# HLK-7621-ALL-KIT-V1_0_020_2_25.net
KiCad netlist of a schematic drawn in Altium Designer
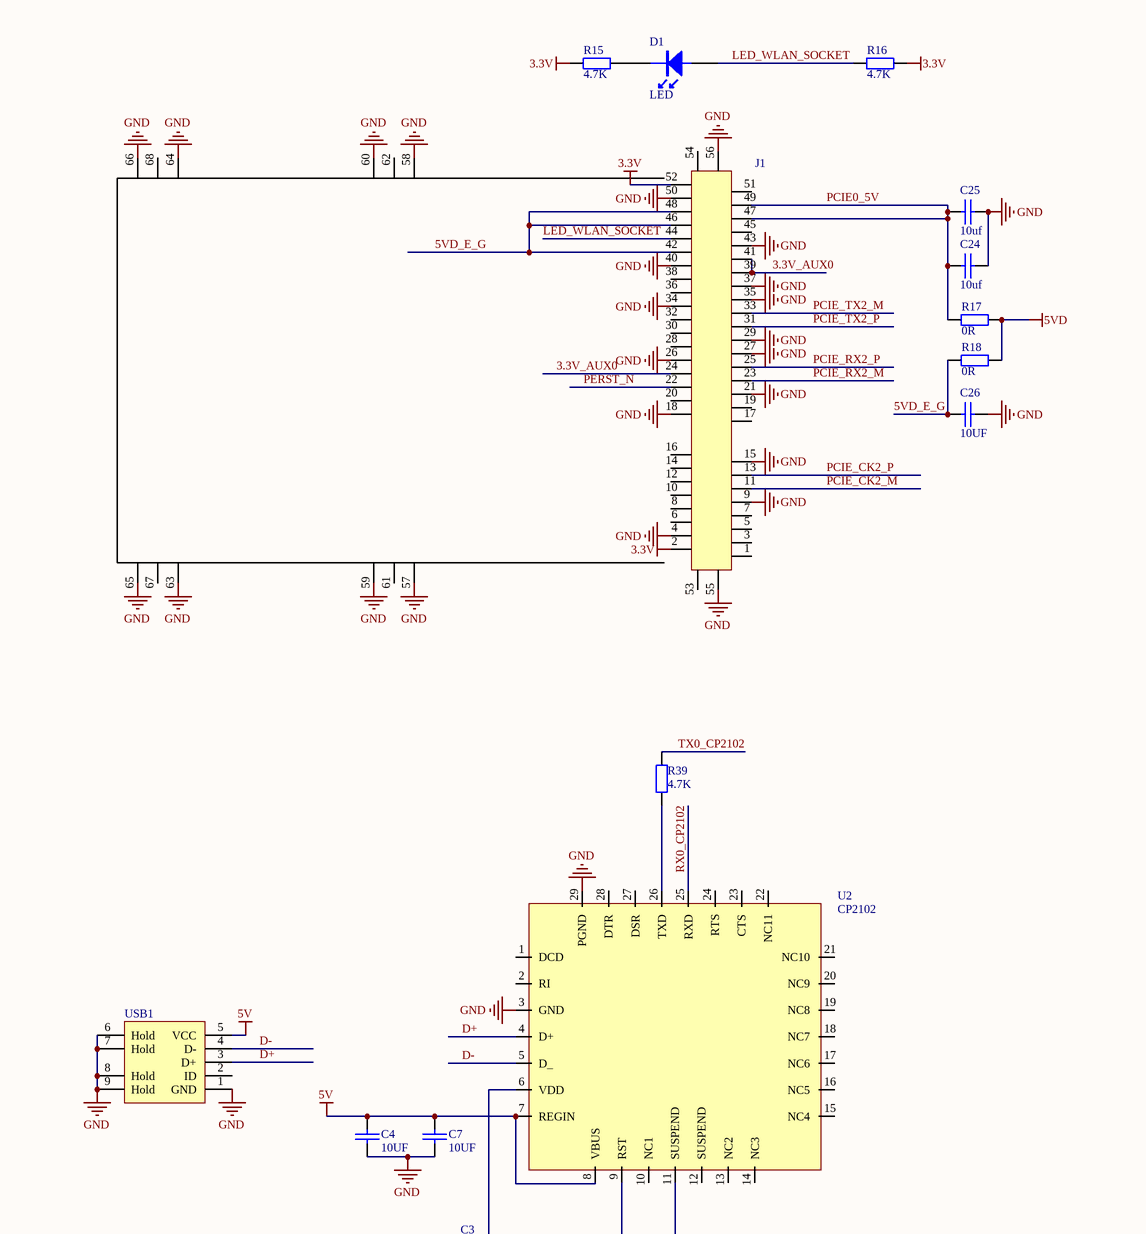
[diagram p0: HLK-7621-ALL-KIT-V1.0(020.2.25).SchDoc, top left]
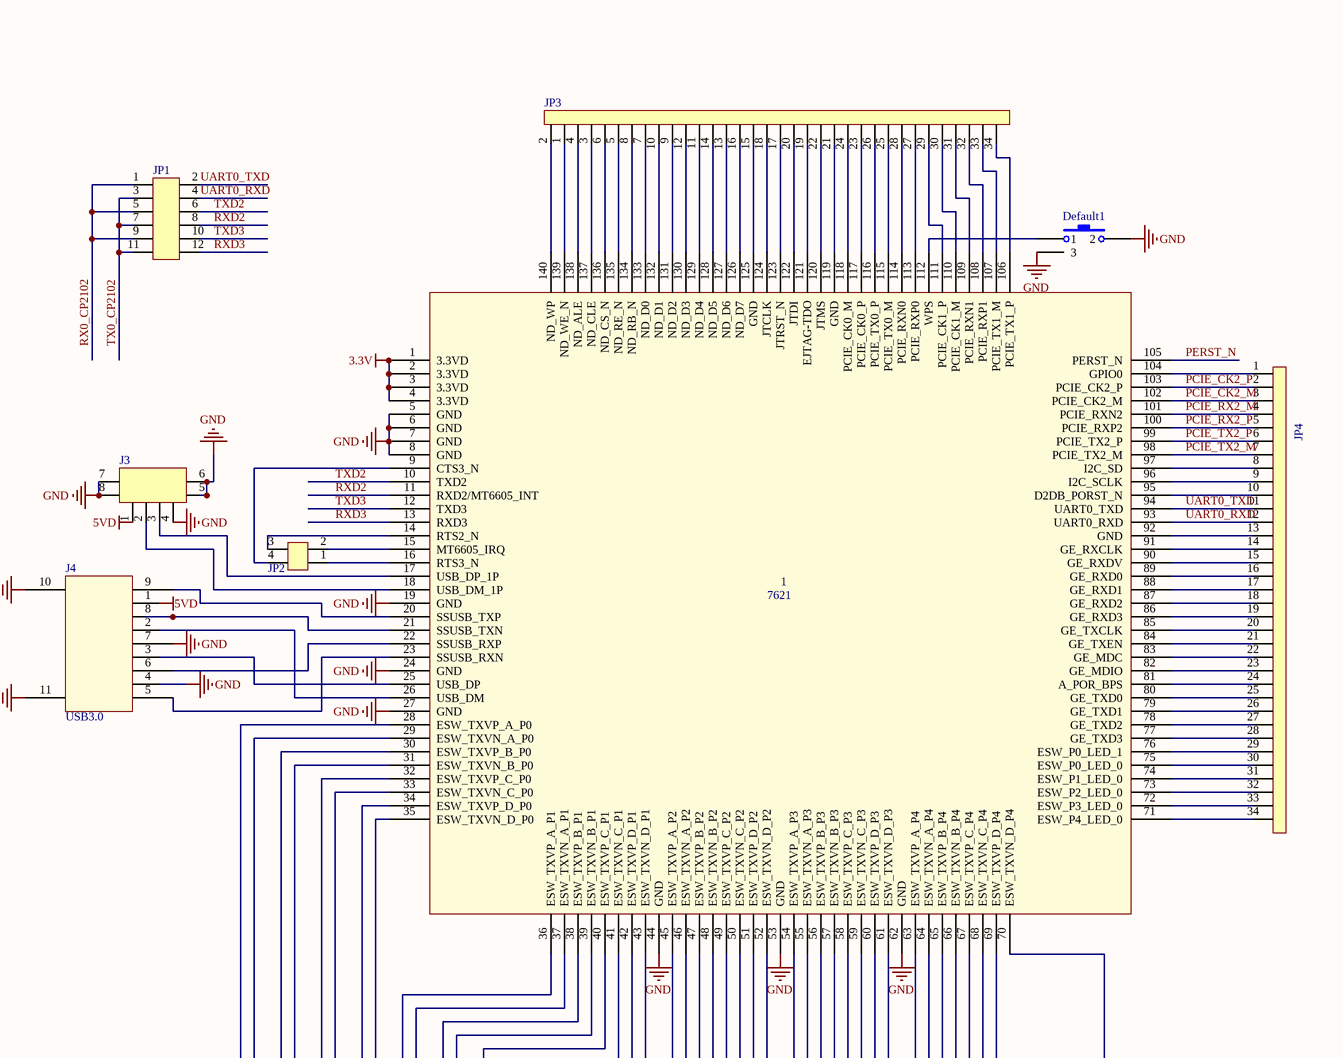
[diagram p1: HLK-7621-ALL-KIT-V1.0(020.2.25).SchDoc, top right]
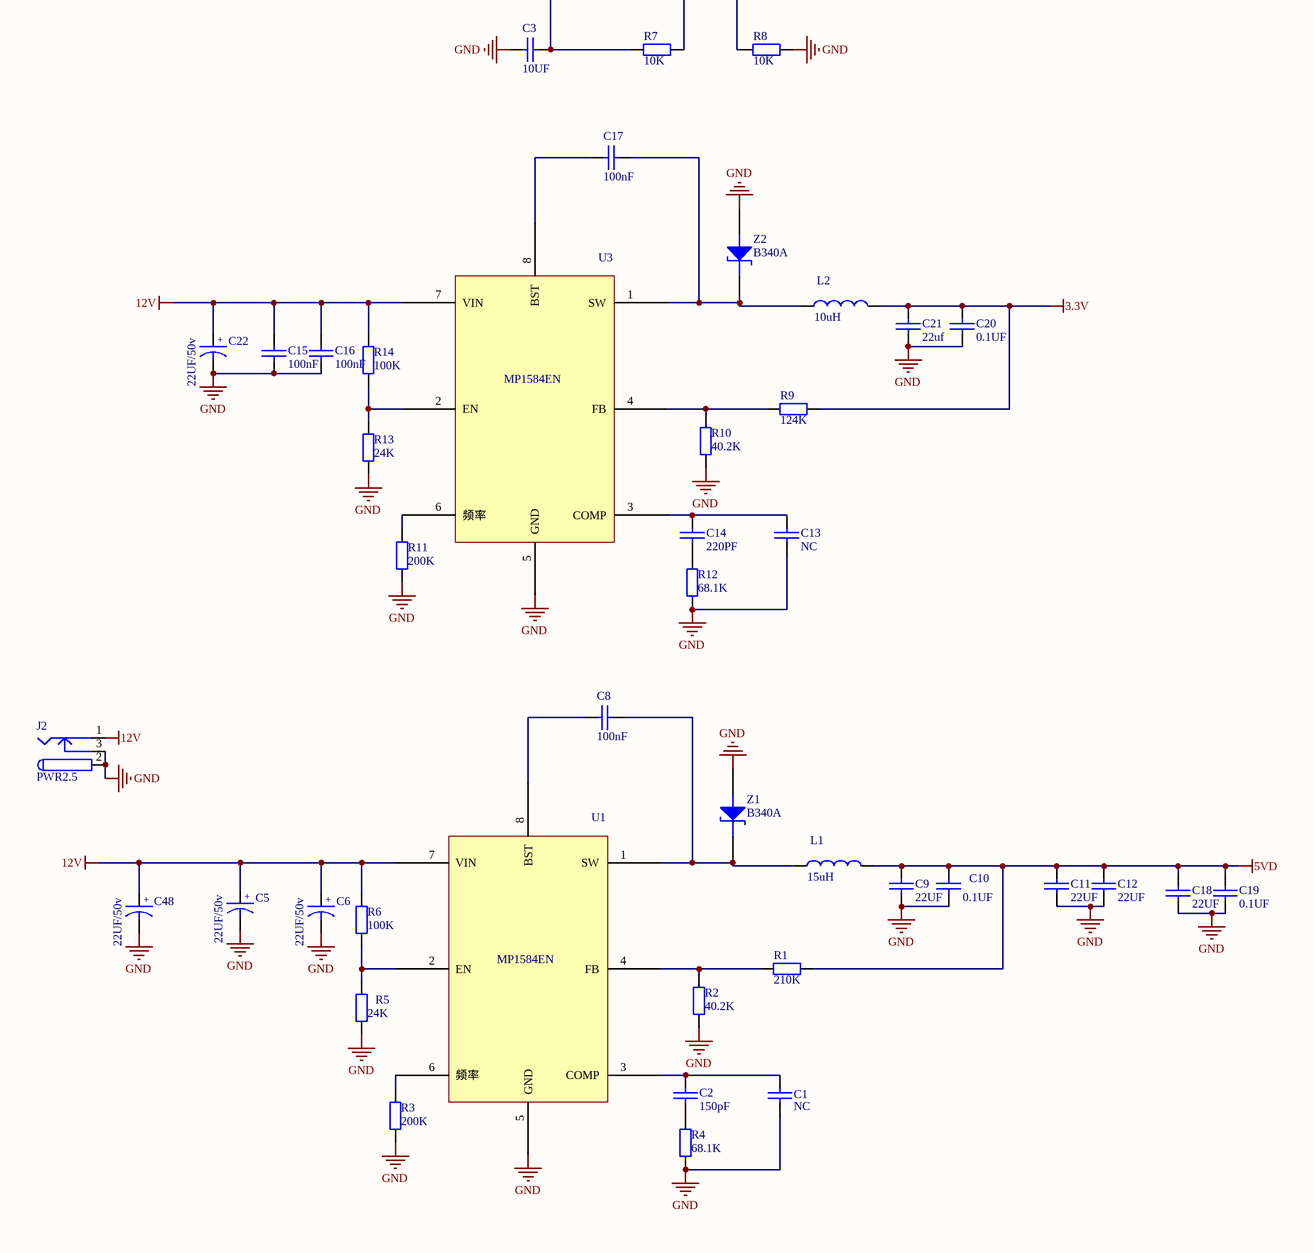
[diagram p2: HLK-7621-ALL-KIT-V1.0(020.2.25).SchDoc, bottom left]
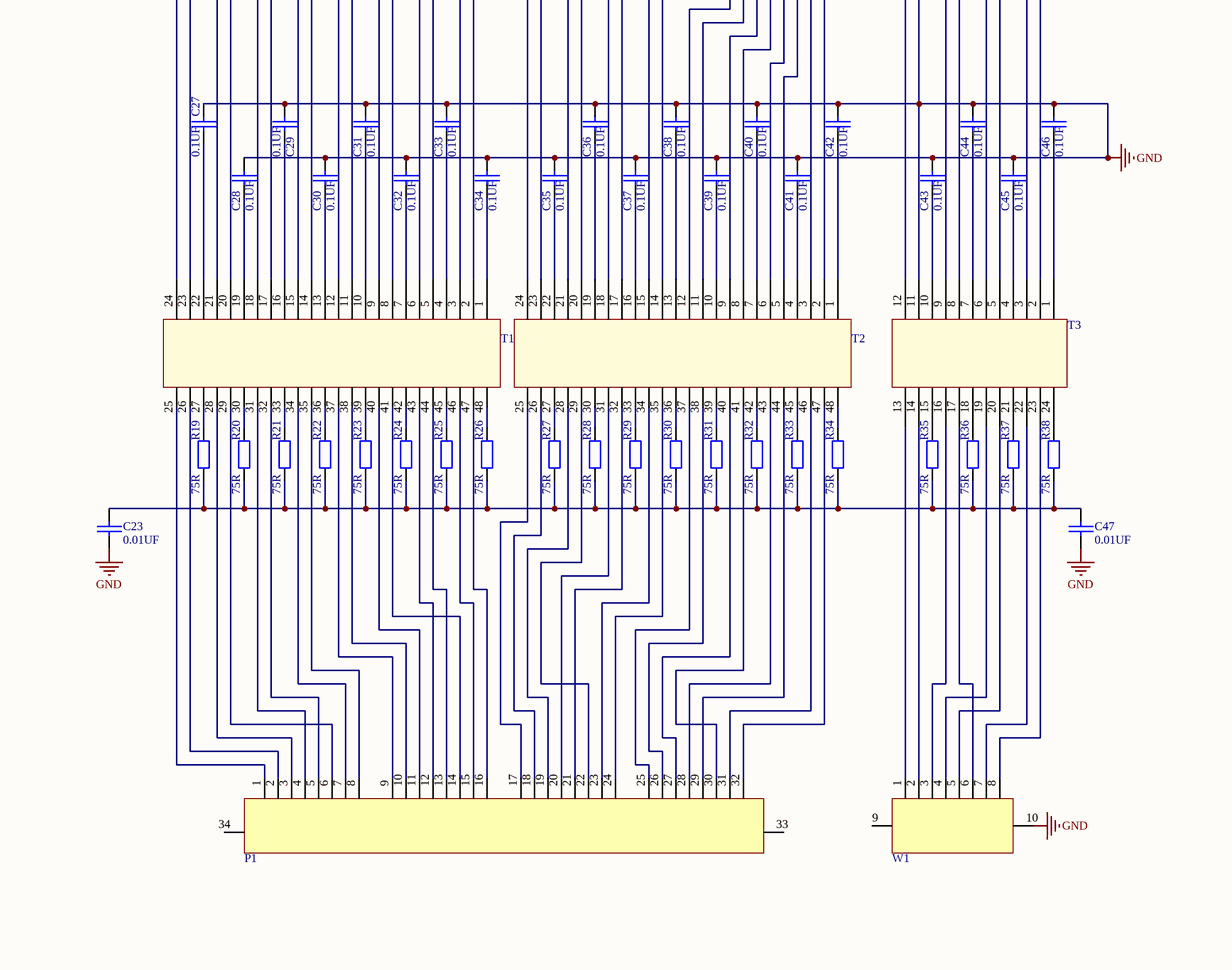
[diagram p3: HLK-7621-ALL-KIT-V1.0(020.2.25).SchDoc, bottom right]

(export (version "E")
  (design (tool "Eeschema 10.0.6"))
  (components
    (comp (ref "1") (value "7621") (footprint "HLK-7621") (libsource (lib "Schlib1") (part "7621")))
    (comp (ref "C1")
      (value "NC")
      (footprint "0603")
      (description "Capacitor")
      (libsource (lib "*") (part "CAP"))
    )
    (comp (ref "C2")
      (value "150pF")
      (footprint "0603")
      (description "Capacitor")
      (libsource (lib "*") (part "CAP"))
    )
    (comp (ref "C3")
      (value "10UF")
      (footprint "0603L")
      (description "Capacitor")
      (libsource (lib "*") (part "CAP"))
    )
    (comp (ref "C4")
      (value "10UF")
      (footprint "0603L")
      (description "Capacitor")
      (libsource (lib "*") (part "CAP"))
    )
    (comp (ref "C5")
      (value "22UF/50v")
      (footprint "0603")
      (description "Capacitor")
      (libsource (lib "Miscellaneous Devices") (part "CAPACITOR POL"))
    )
    (comp (ref "C6")
      (value "22UF/50v")
      (footprint "0603")
      (description "Capacitor")
      (libsource (lib "Miscellaneous Devices") (part "CAPACITOR POL"))
    )
    (comp (ref "C7")
      (value "10UF")
      (footprint "0603L")
      (description "Capacitor")
      (libsource (lib "*") (part "CAP"))
    )
    (comp (ref "C8")
      (value "100nF")
      (footprint "0603")
      (description "Capacitor")
      (libsource (lib "*") (part "CAP"))
    )
    (comp (ref "C9")
      (value "22UF")
      (footprint "0603")
      (description "Capacitor")
      (libsource (lib "*") (part "CAP"))
    )
    (comp (ref "C10")
      (value "0.1UF")
      (footprint "0603")
      (description "Capacitor")
      (libsource (lib "*") (part "CAP"))
    )
    (comp (ref "C11")
      (value "22UF")
      (footprint "0603")
      (description "Capacitor")
      (libsource (lib "*") (part "CAP"))
    )
    (comp (ref "C12")
      (value "22UF")
      (footprint "0603")
      (description "Capacitor")
      (libsource (lib "*") (part "CAP"))
    )
    (comp (ref "C13")
      (value "NC")
      (footprint "0603")
      (description "Capacitor")
      (libsource (lib "*") (part "CAP"))
    )
    (comp (ref "C14")
      (value "220PF")
      (footprint "0603")
      (description "Capacitor")
      (libsource (lib "*") (part "CAP"))
    )
    (comp (ref "C15")
      (value "100nF")
      (footprint "0603")
      (description "Capacitor")
      (libsource (lib "*") (part "CAP"))
    )
    (comp (ref "C16")
      (value "100nF")
      (footprint "0603")
      (description "Capacitor")
      (libsource (lib "*") (part "CAP"))
    )
    (comp (ref "C17")
      (value "100nF")
      (footprint "0603")
      (description "Capacitor")
      (libsource (lib "*") (part "CAP"))
    )
    (comp (ref "C18")
      (value "22UF")
      (footprint "0603")
      (description "Capacitor")
      (libsource (lib "*") (part "CAP"))
    )
    (comp (ref "C19")
      (value "0.1UF")
      (footprint "0603")
      (description "Capacitor")
      (libsource (lib "*") (part "CAP"))
    )
    (comp (ref "C20")
      (value "0.1UF")
      (footprint "0603")
      (description "Capacitor")
      (libsource (lib "*") (part "CAP"))
    )
    (comp (ref "C21")
      (value "22uf")
      (footprint "0603")
      (description "Capacitor")
      (libsource (lib "*") (part "CAP"))
    )
    (comp (ref "C22")
      (value "22UF/50v")
      (footprint "CAP_SMT_8*10.5")
      (description "Capacitor")
      (libsource (lib "Miscellaneous Devices") (part "CAPACITOR POL"))
    )
    (comp (ref "C23")
      (value "0.01UF")
      (footprint "C1206")
      (description "Capacitor")
      (libsource (lib "*") (part "CAP"))
    )
    (comp (ref "C24")
      (value "10uf")
      (footprint "C1206")
      (description "Capacitor")
      (libsource (lib "*") (part "CAP"))
    )
    (comp (ref "C25")
      (value "10uf")
      (footprint "C1206")
      (description "Capacitor")
      (libsource (lib "*") (part "CAP"))
    )
    (comp (ref "C26")
      (value "10UF")
      (footprint "C1206")
      (description "Capacitor")
      (libsource (lib "*") (part "CAP"))
    )
    (comp (ref "C27")
      (value "0.1UF")
      (footprint "C0402")
      (description "Capacitor")
      (libsource (lib "*") (part "CAP"))
    )
    (comp (ref "C28")
      (value "0.1UF")
      (footprint "C0402")
      (description "Capacitor")
      (libsource (lib "*") (part "CAP"))
    )
    (comp (ref "C29")
      (value "0.1UF")
      (footprint "C0402")
      (description "Capacitor")
      (libsource (lib "*") (part "CAP"))
    )
    (comp (ref "C30")
      (value "0.1UF")
      (footprint "C0402")
      (description "Capacitor")
      (libsource (lib "*") (part "CAP"))
    )
    (comp (ref "C31")
      (value "0.1UF")
      (footprint "C0402")
      (description "Capacitor")
      (libsource (lib "*") (part "CAP"))
    )
    (comp (ref "C32")
      (value "0.1UF")
      (footprint "C0402")
      (description "Capacitor")
      (libsource (lib "*") (part "CAP"))
    )
    (comp (ref "C33")
      (value "0.1UF")
      (footprint "C0402")
      (description "Capacitor")
      (libsource (lib "*") (part "CAP"))
    )
    (comp (ref "C34")
      (value "0.1UF")
      (footprint "C0402")
      (description "Capacitor")
      (libsource (lib "*") (part "CAP"))
    )
    (comp (ref "C35")
      (value "0.1UF")
      (footprint "C0402")
      (description "Capacitor")
      (libsource (lib "*") (part "CAP"))
    )
    (comp (ref "C36")
      (value "0.1UF")
      (footprint "C0402")
      (description "Capacitor")
      (libsource (lib "*") (part "CAP"))
    )
    (comp (ref "C37")
      (value "0.1UF")
      (footprint "C0402")
      (description "Capacitor")
      (libsource (lib "*") (part "CAP"))
    )
    (comp (ref "C38")
      (value "0.1UF")
      (footprint "C0402")
      (description "Capacitor")
      (libsource (lib "*") (part "CAP"))
    )
    (comp (ref "C39")
      (value "0.1UF")
      (footprint "C0402")
      (description "Capacitor")
      (libsource (lib "*") (part "CAP"))
    )
    (comp (ref "C40")
      (value "0.1UF")
      (footprint "C0402")
      (description "Capacitor")
      (libsource (lib "*") (part "CAP"))
    )
    (comp (ref "C41")
      (value "0.1UF")
      (footprint "C0402")
      (description "Capacitor")
      (libsource (lib "*") (part "CAP"))
    )
    (comp (ref "C42")
      (value "0.1UF")
      (footprint "C0402")
      (description "Capacitor")
      (libsource (lib "*") (part "CAP"))
    )
    (comp (ref "C43")
      (value "0.1UF")
      (footprint "C0402")
      (description "Capacitor")
      (libsource (lib "*") (part "CAP"))
    )
    (comp (ref "C44")
      (value "0.1UF")
      (footprint "C0402")
      (description "Capacitor")
      (libsource (lib "*") (part "CAP"))
    )
    (comp (ref "C45")
      (value "0.1UF")
      (footprint "C0402")
      (description "Capacitor")
      (libsource (lib "*") (part "CAP"))
    )
    (comp (ref "C46")
      (value "0.1UF")
      (footprint "C0402")
      (description "Capacitor")
      (libsource (lib "*") (part "CAP"))
    )
    (comp (ref "C47")
      (value "0.01UF")
      (footprint "C1206")
      (description "Capacitor")
      (libsource (lib "*") (part "CAP"))
    )
    (comp (ref "C48")
      (value "22UF/50v")
      (footprint "CAP_SMT_8*10.5")
      (description "Capacitor")
      (libsource (lib "Miscellaneous Devices") (part "CAPACITOR POL"))
    )
    (comp (ref "D1") (value "LED") (footprint "C1206") (libsource (lib "*") (part "LED")))
    (comp (ref "Default1")
      (value "SW-PB")
      (footprint "K5")
      (description "Switch")
      (fields (field (name "PUBLISHER") "Altium Limited"))
      (libsource (lib "Miscellaneous Devices") (part "SW-PB"))
    )
    (comp (ref "J1")
      (value "~")
      (footprint "CONSG/54/MINICARD/AS0B22-S68-7F/HALF/FUL")
      (libsource (lib "") (part "Component_1_2"))
    )
    (comp (ref "J2")
      (value "PWR2.5")
      (description "Low Voltage Power Supply Connector")
      (fields (field (name "PUBLISHER") "Altium Limited"))
      (libsource (lib "*") (part "PWR2.5"))
    )
    (comp (ref "J3") (value "~") (libsource (lib "Schlib1") (part "2")))
    (comp (ref "J4") (value "USB3.0") (libsource (lib "Schlib1") (part "USB3.0/9P/DIP/MAINSUPER")))
    (comp (ref "JP1") (value "~") (footprint "HDR2X6") (libsource (lib "Schlib1") (part "Component_1")))
    (comp (ref "JP2") (value "~") (footprint "HDR2X2") (libsource (lib "") (part "2_1")))
    (comp (ref "JP3") (value "~") (footprint "HDR2X17") (libsource (lib "") (part "2_2")))
    (comp (ref "JP4") (value "2") (footprint "HDR2X17") (libsource (lib "") (part "2_3")))
    (comp (ref "L1") (value "15uH") (footprint "CD105") (libsource (lib "startkit") (part "INDUCTOR1")))
    (comp (ref "L2") (value "10uH") (footprint "CD105") (libsource (lib "startkit") (part "INDUCTOR1")))
    (comp (ref "P1")
      (value "Component_2")
      (footprint "PHJ8X4_N")
      (libsource (lib "Schlib1") (part "Component_2"))
    )
    (comp (ref "R1")
      (value "210K")
      (footprint "0603")
      (description "Resistor")
      (fields (field (name "PUBLISHER") "Altium Limited"))
      (libsource (lib "Miscellaneous Devices") (part "Res2"))
    )
    (comp (ref "R2")
      (value "40.2K")
      (footprint "0603")
      (description "Resistor")
      (fields (field (name "PUBLISHER") "Altium Limited"))
      (libsource (lib "") (part "Res2_1"))
    )
    (comp (ref "R3")
      (value "200K")
      (footprint "0603")
      (description "Resistor")
      (fields (field (name "PUBLISHER") "Altium Limited"))
      (libsource (lib "") (part "Res2_1"))
    )
    (comp (ref "R4")
      (value "68.1K")
      (footprint "0603")
      (description "Resistor")
      (fields (field (name "PUBLISHER") "Altium Limited"))
      (libsource (lib "") (part "Res2_1"))
    )
    (comp (ref "R5")
      (value "24K")
      (footprint "0603")
      (description "Resistor")
      (fields (field (name "PUBLISHER") "Altium Limited"))
      (libsource (lib "") (part "Res2_1"))
    )
    (comp (ref "R6")
      (value "100K")
      (footprint "0603")
      (description "Resistor")
      (fields (field (name "PUBLISHER") "Altium Limited"))
      (libsource (lib "") (part "Res2_1"))
    )
    (comp (ref "R7")
      (value "10K")
      (footprint "0603L")
      (description "Resistor")
      (fields (field (name "PUBLISHER") "Altium Limited"))
      (libsource (lib "") (part "Res2_2"))
    )
    (comp (ref "R8")
      (value "10K")
      (footprint "0603L")
      (description "Resistor")
      (fields (field (name "PUBLISHER") "Altium Limited"))
      (libsource (lib "Miscellaneous Devices") (part "Res2"))
    )
    (comp (ref "R9")
      (value "124K")
      (footprint "0603")
      (description "Resistor")
      (fields (field (name "PUBLISHER") "Altium Limited"))
      (libsource (lib "Miscellaneous Devices") (part "Res2"))
    )
    (comp (ref "R10")
      (value "40.2K")
      (footprint "0603")
      (description "Resistor")
      (fields (field (name "PUBLISHER") "Altium Limited"))
      (libsource (lib "") (part "Res2_1"))
    )
    (comp (ref "R11")
      (value "200K")
      (footprint "0603")
      (description "Resistor")
      (fields (field (name "PUBLISHER") "Altium Limited"))
      (libsource (lib "") (part "Res2_1"))
    )
    (comp (ref "R12")
      (value "68.1K")
      (footprint "0603")
      (description "Resistor")
      (fields (field (name "PUBLISHER") "Altium Limited"))
      (libsource (lib "") (part "Res2_1"))
    )
    (comp (ref "R13")
      (value "24K")
      (footprint "0603")
      (description "Resistor")
      (fields (field (name "PUBLISHER") "Altium Limited"))
      (libsource (lib "") (part "Res2_1"))
    )
    (comp (ref "R14")
      (value "100K")
      (footprint "0603")
      (description "Resistor")
      (fields (field (name "PUBLISHER") "Altium Limited"))
      (libsource (lib "") (part "Res2_1"))
    )
    (comp (ref "R15")
      (value "4.7K")
      (footprint "0603")
      (description "Resistor")
      (fields (field (name "PUBLISHER") "Altium Limited"))
      (libsource (lib "Miscellaneous Devices") (part "Res2"))
    )
    (comp (ref "R16")
      (value "4.7K")
      (footprint "0603")
      (description "Resistor")
      (fields (field (name "PUBLISHER") "Altium Limited"))
      (libsource (lib "Miscellaneous Devices") (part "Res2"))
    )
    (comp (ref "R17")
      (value "0R")
      (footprint "L0805")
      (description "Resistor")
      (fields (field (name "PUBLISHER") "Altium Limited"))
      (libsource (lib "") (part "Res2_2"))
    )
    (comp (ref "R18")
      (value "0R")
      (footprint "R1206")
      (description "Resistor")
      (fields (field (name "PUBLISHER") "Altium Limited"))
      (libsource (lib "Miscellaneous Devices") (part "Res2"))
    )
    (comp (ref "R19")
      (value "75R")
      (footprint "R0402")
      (description "Resistor")
      (fields (field (name "PUBLISHER") "Altium Limited"))
      (libsource (lib "Schlib1") (part "Res2"))
    )
    (comp (ref "R20")
      (value "75R")
      (footprint "R0402")
      (description "Resistor")
      (fields (field (name "PUBLISHER") "Altium Limited"))
      (libsource (lib "Schlib1") (part "Res2"))
    )
    (comp (ref "R21")
      (value "75R")
      (footprint "R0402")
      (description "Resistor")
      (fields (field (name "PUBLISHER") "Altium Limited"))
      (libsource (lib "Schlib1") (part "Res2"))
    )
    (comp (ref "R22")
      (value "75R")
      (footprint "R0402")
      (description "Resistor")
      (fields (field (name "PUBLISHER") "Altium Limited"))
      (libsource (lib "Schlib1") (part "Res2"))
    )
    (comp (ref "R23")
      (value "75R")
      (footprint "R0402")
      (description "Resistor")
      (fields (field (name "PUBLISHER") "Altium Limited"))
      (libsource (lib "Schlib1") (part "Res2"))
    )
    (comp (ref "R24")
      (value "75R")
      (footprint "R0402")
      (description "Resistor")
      (fields (field (name "PUBLISHER") "Altium Limited"))
      (libsource (lib "Schlib1") (part "Res2"))
    )
    (comp (ref "R25")
      (value "75R")
      (footprint "R0402")
      (description "Resistor")
      (fields (field (name "PUBLISHER") "Altium Limited"))
      (libsource (lib "Schlib1") (part "Res2"))
    )
    (comp (ref "R26")
      (value "75R")
      (footprint "R0402")
      (description "Resistor")
      (fields (field (name "PUBLISHER") "Altium Limited"))
      (libsource (lib "Schlib1") (part "Res2"))
    )
    (comp (ref "R27")
      (value "75R")
      (footprint "R0402")
      (description "Resistor")
      (fields (field (name "PUBLISHER") "Altium Limited"))
      (libsource (lib "Schlib1") (part "Res2"))
    )
    (comp (ref "R28")
      (value "75R")
      (footprint "R0402")
      (description "Resistor")
      (fields (field (name "PUBLISHER") "Altium Limited"))
      (libsource (lib "Schlib1") (part "Res2"))
    )
    (comp (ref "R29")
      (value "75R")
      (footprint "R0402")
      (description "Resistor")
      (fields (field (name "PUBLISHER") "Altium Limited"))
      (libsource (lib "Schlib1") (part "Res2"))
    )
    (comp (ref "R30")
      (value "75R")
      (footprint "R0402")
      (description "Resistor")
      (fields (field (name "PUBLISHER") "Altium Limited"))
      (libsource (lib "Schlib1") (part "Res2"))
    )
    (comp (ref "R31")
      (value "75R")
      (footprint "R0402")
      (description "Resistor")
      (fields (field (name "PUBLISHER") "Altium Limited"))
      (libsource (lib "Schlib1") (part "Res2"))
    )
    (comp (ref "R32")
      (value "75R")
      (footprint "R0402")
      (description "Resistor")
      (fields (field (name "PUBLISHER") "Altium Limited"))
      (libsource (lib "Schlib1") (part "Res2"))
    )
    (comp (ref "R33")
      (value "75R")
      (footprint "R0402")
      (description "Resistor")
      (fields (field (name "PUBLISHER") "Altium Limited"))
      (libsource (lib "Schlib1") (part "Res2"))
    )
    (comp (ref "R34")
      (value "75R")
      (footprint "R0402")
      (description "Resistor")
      (fields (field (name "PUBLISHER") "Altium Limited"))
      (libsource (lib "Schlib1") (part "Res2"))
    )
    (comp (ref "R35")
      (value "75R")
      (footprint "R0402")
      (description "Resistor")
      (fields (field (name "PUBLISHER") "Altium Limited"))
      (libsource (lib "Schlib1") (part "Res2"))
    )
    (comp (ref "R36")
      (value "75R")
      (footprint "R0402")
      (description "Resistor")
      (fields (field (name "PUBLISHER") "Altium Limited"))
      (libsource (lib "Schlib1") (part "Res2"))
    )
    (comp (ref "R37")
      (value "75R")
      (footprint "R0402")
      (description "Resistor")
      (fields (field (name "PUBLISHER") "Altium Limited"))
      (libsource (lib "Schlib1") (part "Res2"))
    )
    (comp (ref "R38")
      (value "75R")
      (footprint "R0402")
      (description "Resistor")
      (fields (field (name "PUBLISHER") "Altium Limited"))
      (libsource (lib "Schlib1") (part "Res2"))
    )
    (comp (ref "R39")
      (value "4.7K")
      (footprint "0603")
      (description "Resistor")
      (fields (field (name "PUBLISHER") "Altium Limited"))
      (libsource (lib "") (part "Res2_3"))
    )
    (comp (ref "T1")
      (value "TRANSFORMER/24P/SMD/HN2429CG")
      (footprint "TRANSFORMER/48P/SMD/GS5014LF")
      (libsource (lib "Schlib1") (part "TRANSFORMER/24P/SMD/HN2429CG"))
    )
    (comp (ref "T2")
      (value "TRANSFORMER/24P/SMD/HN2429CG")
      (footprint "TRANSFORMER/48P/SMD/GS5014LF")
      (libsource (lib "Schlib1") (part "TRANSFORMER/24P/SMD/HN2429CG"))
    )
    (comp (ref "T3")
      (value "TRANSFORMER/24P/SMD/HN2429CG")
      (footprint "TRANSFORMER/24P/SMD/HN2429CG")
      (libsource (lib "") (part "TRANSFORMER/24P/SMD/HN2429CG_1"))
    )
    (comp (ref "U1") (value "MP1584EN") (footprint "SOP8_150") (libsource (lib "") (part "Component_1_1")))
    (comp (ref "U2") (value "CP2102") (footprint "cp2102") (libsource (lib "") (part "Component_1_3")))
    (comp (ref "U3") (value "MP1584EN") (footprint "SOP8_150") (libsource (lib "") (part "Component_1_1")))
    (comp (ref "USB1") (value "USB1") (footprint "usb") (libsource (lib "Schlib1") (part "USB-B")))
    (comp (ref "W1")
      (value "Component_3")
      (footprint "PCBComponent_1")
      (libsource (lib "Schlib1") (part "Component_3"))
    )
    (comp (ref "Z1")
      (value "B340A")
      (footprint "SMA")
      (description "Zener Diode")
      (libsource (lib "杂元件库") (part "ZENER2"))
    )
    (comp (ref "Z2")
      (value "B340A")
      (footprint "SMA")
      (description "Zener Diode")
      (libsource (lib "杂元件库") (part "ZENER2"))
    )
  )
  (nets
    (net (code "1") (name "/3.3V_AUX0") (class "Default")
      (node (ref "J1") (pin "24") (pinfunction "24_24") (pintype "passive"))
      (node (ref "J1") (pin "39") (pinfunction "39_39") (pintype "passive"))
      (node (ref "J1") (pin "41") (pinfunction "41_41") (pintype "passive"))
    )
    (net (code "2") (name "/5VD_E_G") (class "Default")
      (node (ref "C26") (pin "1") (pinfunction "1_1") (pintype "passive"))
      (node (ref "J1") (pin "42") (pinfunction "42_42") (pintype "passive"))
      (node (ref "J1") (pin "46") (pinfunction "46_46") (pintype "passive"))
      (node (ref "J1") (pin "48") (pinfunction "48_48") (pintype "passive"))
      (node (ref "R18") (pin "2") (pinfunction "2_2") (pintype "passive"))
    )
    (net (code "3") (name "/D+") (class "Default")
      (node (ref "U2") (pin "4") (pinfunction "D+_4") (pintype "passive"))
      (node (ref "USB1") (pin "3") (pinfunction "D+_3") (pintype "passive"))
    )
    (net (code "4") (name "/D-") (class "Default")
      (node (ref "U2") (pin "5") (pinfunction "D__5") (pintype "passive"))
      (node (ref "USB1") (pin "4") (pinfunction "D-_4") (pintype "passive"))
    )
    (net (code "5") (name "/LED_WLAN_SOCKET") (class "Default")
      (node (ref "D1") (pin "1") (pinfunction "1_1") (pintype "passive"))
      (node (ref "J1") (pin "44") (pinfunction "44_44") (pintype "passive"))
      (node (ref "R16") (pin "2") (pinfunction "2_2") (pintype "passive"))
    )
    (net (code "6") (name "/PCIE0_5V") (class "Default")
      (node (ref "C24") (pin "1") (pinfunction "1_1") (pintype "passive"))
      (node (ref "C25") (pin "1") (pinfunction "1_1") (pintype "passive"))
      (node (ref "J1") (pin "47") (pinfunction "47_47") (pintype "passive"))
      (node (ref "J1") (pin "49") (pinfunction "49_49") (pintype "passive"))
      (node (ref "R17") (pin "1") (pinfunction "1_1") (pintype "passive"))
    )
    (net (code "7") (name "/PCIE_CK2_M") (class "Default")
      (node (ref "1") (pin "102") (pinfunction "PCIE_CK2_M_102") (pintype "passive"))
      (node (ref "J1") (pin "11") (pinfunction "11_11") (pintype "passive"))
      (node (ref "JP4") (pin "3") (pinfunction "3_3") (pintype "passive"))
    )
    (net (code "8") (name "/PCIE_CK2_P") (class "Default")
      (node (ref "1") (pin "103") (pinfunction "PCIE_CK2_P_103") (pintype "passive"))
      (node (ref "J1") (pin "13") (pinfunction "13_13") (pintype "passive"))
      (node (ref "JP4") (pin "2") (pinfunction "2_2") (pintype "passive"))
    )
    (net (code "9") (name "/PCIE_RX2_M") (class "Default")
      (node (ref "1") (pin "101") (pinfunction "PCIE_RXN2_101") (pintype "passive"))
      (node (ref "J1") (pin "23") (pinfunction "23_23") (pintype "passive"))
      (node (ref "JP4") (pin "4") (pinfunction "4_4") (pintype "passive"))
    )
    (net (code "10") (name "/PCIE_RX2_P") (class "Default")
      (node (ref "1") (pin "100") (pinfunction "PCIE_RXP2_100") (pintype "passive"))
      (node (ref "J1") (pin "25") (pinfunction "25_25") (pintype "passive"))
      (node (ref "JP4") (pin "5") (pinfunction "5_5") (pintype "passive"))
    )
    (net (code "11") (name "/PCIE_TX2_M") (class "Default")
      (node (ref "1") (pin "98") (pinfunction "PCIE_TX2_M_98") (pintype "passive"))
      (node (ref "J1") (pin "33") (pinfunction "33_33") (pintype "passive"))
      (node (ref "JP4") (pin "7") (pinfunction "7_7") (pintype "passive"))
    )
    (net (code "12") (name "/PCIE_TX2_P") (class "Default")
      (node (ref "1") (pin "99") (pinfunction "PCIE_TX2_P_99") (pintype "passive"))
      (node (ref "J1") (pin "31") (pinfunction "31_31") (pintype "passive"))
      (node (ref "JP4") (pin "6") (pinfunction "6_6") (pintype "passive"))
    )
    (net (code "13") (name "/PERST_N") (class "Default")
      (node (ref "1") (pin "105") (pinfunction "PERST_N_105") (pintype "passive"))
      (node (ref "J1") (pin "22") (pinfunction "22_22") (pintype "passive"))
    )
    (net (code "14") (name "/RX0_CP2102") (class "Default")
      (node (ref "JP1") (pin "1") (pinfunction "1_1") (pintype "passive"))
      (node (ref "JP1") (pin "5") (pinfunction "5_5") (pintype "passive"))
      (node (ref "JP1") (pin "9") (pinfunction "9_9") (pintype "passive"))
      (node (ref "U2") (pin "25") (pinfunction "RXD_25") (pintype "passive"))
    )
    (net (code "15") (name "/RXD2") (class "Default")
      (node (ref "1") (pin "11") (pinfunction "RXD2/MT6605_INT_11") (pintype "passive"))
      (node (ref "JP1") (pin "8") (pinfunction "8_8") (pintype "passive"))
    )
    (net (code "16") (name "/RXD3") (class "Default")
      (node (ref "1") (pin "13") (pinfunction "RXD3_13") (pintype "passive"))
      (node (ref "JP1") (pin "12") (pinfunction "12_12") (pintype "passive"))
    )
    (net (code "17") (name "/TX0_CP2102") (class "Default")
      (node (ref "JP1") (pin "11") (pinfunction "11_11") (pintype "passive"))
      (node (ref "JP1") (pin "3") (pinfunction "3_3") (pintype "passive"))
      (node (ref "JP1") (pin "7") (pinfunction "7_7") (pintype "passive"))
      (node (ref "R39") (pin "1") (pinfunction "1_1") (pintype "passive"))
    )
    (net (code "18") (name "/TXD2") (class "Default")
      (node (ref "1") (pin "10") (pinfunction "TXD2_10") (pintype "passive"))
      (node (ref "JP1") (pin "6") (pinfunction "6_6") (pintype "passive"))
    )
    (net (code "19") (name "/TXD3") (class "Default")
      (node (ref "1") (pin "12") (pinfunction "TXD3_12") (pintype "passive"))
      (node (ref "JP1") (pin "10") (pinfunction "10_10") (pintype "passive"))
    )
    (net (code "20") (name "/UART0_RXD") (class "Default")
      (node (ref "1") (pin "93") (pinfunction "UART0_RXD_93") (pintype "passive"))
      (node (ref "JP1") (pin "4") (pinfunction "4_4") (pintype "passive"))
      (node (ref "JP4") (pin "12") (pinfunction "12_12") (pintype "passive"))
    )
    (net (code "21") (name "/UART0_TXD") (class "Default")
      (node (ref "1") (pin "94") (pinfunction "UART0_TXD_94") (pintype "passive"))
      (node (ref "JP1") (pin "2") (pinfunction "2_2") (pintype "passive"))
      (node (ref "JP4") (pin "11") (pinfunction "11_11") (pintype "passive"))
    )
    (net (code "22") (name "3.3V") (class "Default")
      (node (ref "1") (pin "1") (pinfunction "3.3VD_1") (pintype "passive"))
      (node (ref "1") (pin "2") (pinfunction "3.3VD_2") (pintype "passive"))
      (node (ref "1") (pin "3") (pinfunction "3.3VD_3") (pintype "passive"))
      (node (ref "1") (pin "4") (pinfunction "3.3VD_4") (pintype "passive"))
      (node (ref "C20") (pin "1") (pinfunction "1_1") (pintype "passive"))
      (node (ref "C21") (pin "1") (pinfunction "1_1") (pintype "passive"))
      (node (ref "J1") (pin "2") (pinfunction "2_2") (pintype "passive"))
      (node (ref "J1") (pin "52") (pinfunction "52_52") (pintype "passive"))
      (node (ref "L2") (pin "1") (pinfunction "1_1") (pintype "passive"))
      (node (ref "R15") (pin "2") (pinfunction "2_2") (pintype "passive"))
      (node (ref "R16") (pin "1") (pinfunction "1_1") (pintype "passive"))
      (node (ref "R9") (pin "1") (pinfunction "1_1") (pintype "passive"))
    )
    (net (code "23") (name "5V") (class "Default")
      (node (ref "C4") (pin "2") (pinfunction "2_2") (pintype "passive"))
      (node (ref "C7") (pin "2") (pinfunction "2_2") (pintype "passive"))
      (node (ref "U2") (pin "7") (pinfunction "REGIN_7") (pintype "passive"))
      (node (ref "U2") (pin "8") (pinfunction "VBUS_8") (pintype "passive"))
      (node (ref "USB1") (pin "5") (pinfunction "VCC_5") (pintype "passive"))
    )
    (net (code "24") (name "5VD") (class "Default")
      (node (ref "C10") (pin "1") (pinfunction "1_1") (pintype "passive"))
      (node (ref "C11") (pin "1") (pinfunction "1_1") (pintype "passive"))
      (node (ref "C12") (pin "1") (pinfunction "1_1") (pintype "passive"))
      (node (ref "C18") (pin "1") (pinfunction "1_1") (pintype "passive"))
      (node (ref "C19") (pin "1") (pinfunction "1_1") (pintype "passive"))
      (node (ref "C9") (pin "1") (pinfunction "1_1") (pintype "passive"))
      (node (ref "J3") (pin "1") (pinfunction "1_1") (pintype "passive"))
      (node (ref "J4") (pin "1") (pinfunction "1_1") (pintype "passive"))
      (node (ref "L1") (pin "1") (pinfunction "1_1") (pintype "passive"))
      (node (ref "R1") (pin "1") (pinfunction "1_1") (pintype "passive"))
      (node (ref "R17") (pin "2") (pinfunction "2_2") (pintype "passive"))
      (node (ref "R18") (pin "1") (pinfunction "1_1") (pintype "passive"))
    )
    (net (code "25") (name "12V") (class "Default")
      (node (ref "C15") (pin "1") (pinfunction "1_1") (pintype "passive"))
      (node (ref "C16") (pin "1") (pinfunction "1_1") (pintype "passive"))
      (node (ref "C22") (pin "1") (pinfunction "1_1") (pintype "passive"))
      (node (ref "C48") (pin "1") (pinfunction "1_1") (pintype "passive"))
      (node (ref "C5") (pin "1") (pinfunction "1_1") (pintype "passive"))
      (node (ref "C6") (pin "1") (pinfunction "1_1") (pintype "passive"))
      (node (ref "J2") (pin "1") (pinfunction "1_1") (pintype "power_in"))
      (node (ref "R14") (pin "2") (pinfunction "2_2") (pintype "passive"))
      (node (ref "R6") (pin "2") (pinfunction "2_2") (pintype "passive"))
      (node (ref "U1") (pin "7") (pinfunction "VIN_7") (pintype "passive"))
      (node (ref "U3") (pin "7") (pinfunction "VIN_7") (pintype "passive"))
    )
    (net (code "26") (name "GND") (class "Default")
      (node (ref "1") (pin "19") (pinfunction "GND_19") (pintype "passive"))
      (node (ref "1") (pin "24") (pinfunction "GND_24") (pintype "passive"))
      (node (ref "1") (pin "27") (pinfunction "GND_27") (pintype "passive"))
      (node (ref "1") (pin "44") (pinfunction "GND_44") (pintype "passive"))
      (node (ref "1") (pin "5") (pinfunction "GND_5") (pintype "passive"))
      (node (ref "1") (pin "53") (pinfunction "GND_53") (pintype "passive"))
      (node (ref "1") (pin "6") (pinfunction "GND_6") (pintype "passive"))
      (node (ref "1") (pin "62") (pinfunction "GND_62") (pintype "passive"))
      (node (ref "1") (pin "64") (pinfunction "ESW_TXVN_A_P4_64") (pintype "passive"))
      (node (ref "1") (pin "7") (pinfunction "GND_7") (pintype "passive"))
      (node (ref "1") (pin "8") (pinfunction "GND_8") (pintype "passive"))
      (node (ref "C1") (pin "2") (pinfunction "2_2") (pintype "passive"))
      (node (ref "C10") (pin "2") (pinfunction "2_2") (pintype "passive"))
      (node (ref "C11") (pin "2") (pinfunction "2_2") (pintype "passive"))
      (node (ref "C12") (pin "2") (pinfunction "2_2") (pintype "passive"))
      (node (ref "C13") (pin "2") (pinfunction "2_2") (pintype "passive"))
      (node (ref "C15") (pin "2") (pinfunction "2_2") (pintype "passive"))
      (node (ref "C16") (pin "2") (pinfunction "2_2") (pintype "passive"))
      (node (ref "C18") (pin "2") (pinfunction "2_2") (pintype "passive"))
      (node (ref "C19") (pin "2") (pinfunction "2_2") (pintype "passive"))
      (node (ref "C20") (pin "2") (pinfunction "2_2") (pintype "passive"))
      (node (ref "C21") (pin "2") (pinfunction "2_2") (pintype "passive"))
      (node (ref "C22") (pin "2") (pinfunction "2_2") (pintype "passive"))
      (node (ref "C23") (pin "2") (pinfunction "2_2") (pintype "passive"))
      (node (ref "C24") (pin "2") (pinfunction "2_2") (pintype "passive"))
      (node (ref "C25") (pin "2") (pinfunction "2_2") (pintype "passive"))
      (node (ref "C26") (pin "2") (pinfunction "2_2") (pintype "passive"))
      (node (ref "C27") (pin "1") (pinfunction "1_1") (pintype "passive"))
      (node (ref "C28") (pin "1") (pinfunction "1_1") (pintype "passive"))
      (node (ref "C29") (pin "1") (pinfunction "1_1") (pintype "passive"))
      (node (ref "C3") (pin "1") (pinfunction "1_1") (pintype "passive"))
      (node (ref "C30") (pin "1") (pinfunction "1_1") (pintype "passive"))
      (node (ref "C31") (pin "1") (pinfunction "1_1") (pintype "passive"))
      (node (ref "C32") (pin "1") (pinfunction "1_1") (pintype "passive"))
      (node (ref "C33") (pin "1") (pinfunction "1_1") (pintype "passive"))
      (node (ref "C34") (pin "1") (pinfunction "1_1") (pintype "passive"))
      (node (ref "C35") (pin "1") (pinfunction "1_1") (pintype "passive"))
      (node (ref "C36") (pin "1") (pinfunction "1_1") (pintype "passive"))
      (node (ref "C37") (pin "1") (pinfunction "1_1") (pintype "passive"))
      (node (ref "C38") (pin "1") (pinfunction "1_1") (pintype "passive"))
      (node (ref "C39") (pin "1") (pinfunction "1_1") (pintype "passive"))
      (node (ref "C4") (pin "1") (pinfunction "1_1") (pintype "passive"))
      (node (ref "C40") (pin "1") (pinfunction "1_1") (pintype "passive"))
      (node (ref "C41") (pin "1") (pinfunction "1_1") (pintype "passive"))
      (node (ref "C42") (pin "1") (pinfunction "1_1") (pintype "passive"))
      (node (ref "C43") (pin "1") (pinfunction "1_1") (pintype "passive"))
      (node (ref "C44") (pin "1") (pinfunction "1_1") (pintype "passive"))
      (node (ref "C45") (pin "1") (pinfunction "1_1") (pintype "passive"))
      (node (ref "C46") (pin "1") (pinfunction "1_1") (pintype "passive"))
      (node (ref "C47") (pin "2") (pinfunction "2_2") (pintype "passive"))
      (node (ref "C48") (pin "2") (pinfunction "2_2") (pintype "passive"))
      (node (ref "C5") (pin "2") (pinfunction "2_2") (pintype "passive"))
      (node (ref "C6") (pin "2") (pinfunction "2_2") (pintype "passive"))
      (node (ref "C7") (pin "1") (pinfunction "1_1") (pintype "passive"))
      (node (ref "C9") (pin "2") (pinfunction "2_2") (pintype "passive"))
      (node (ref "Default1") (pin "2") (pinfunction "2_2") (pintype "passive"))
      (node (ref "Default1") (pin "3") (pinfunction "3_3") (pintype "passive"))
      (node (ref "J1") (pin "15") (pinfunction "15_15") (pintype "passive"))
      (node (ref "J1") (pin "18") (pinfunction "18_18") (pintype "passive"))
      (node (ref "J1") (pin "21") (pinfunction "21_21") (pintype "passive"))
      (node (ref "J1") (pin "26") (pinfunction "26_26") (pintype "passive"))
      (node (ref "J1") (pin "27") (pinfunction "27_27") (pintype "passive"))
      (node (ref "J1") (pin "29") (pinfunction "29_29") (pintype "passive"))
      (node (ref "J1") (pin "34") (pinfunction "34_34") (pintype "passive"))
      (node (ref "J1") (pin "35") (pinfunction "35_35") (pintype "passive"))
      (node (ref "J1") (pin "37") (pinfunction "37_37") (pintype "passive"))
      (node (ref "J1") (pin "4") (pinfunction "4_4") (pintype "passive"))
      (node (ref "J1") (pin "40") (pinfunction "40_40") (pintype "passive"))
      (node (ref "J1") (pin "43") (pinfunction "43_43") (pintype "passive"))
      (node (ref "J1") (pin "50") (pinfunction "50_50") (pintype "passive"))
      (node (ref "J1") (pin "55") (pinfunction "53_55") (pintype "passive"))
      (node (ref "J1") (pin "56") (pinfunction "54_56") (pintype "passive"))
      (node (ref "J1") (pin "57") (pinfunction "57_57") (pintype "passive"))
      (node (ref "J1") (pin "58") (pinfunction "58_58") (pintype "passive"))
      (node (ref "J1") (pin "59") (pinfunction "59_59") (pintype "passive"))
      (node (ref "J1") (pin "60") (pinfunction "60_60") (pintype "passive"))
      (node (ref "J1") (pin "63") (pinfunction "63_63") (pintype "passive"))
      (node (ref "J1") (pin "64") (pinfunction "64_64") (pintype "passive"))
      (node (ref "J1") (pin "65") (pinfunction "65_65") (pintype "passive"))
      (node (ref "J1") (pin "66") (pinfunction "66_66") (pintype "passive"))
      (node (ref "J1") (pin "9") (pinfunction "9_9") (pintype "passive"))
      (node (ref "J2") (pin "2") (pinfunction "2_2") (pintype "power_in"))
      (node (ref "J2") (pin "3") (pinfunction "3_3") (pintype "power_in"))
      (node (ref "J3") (pin "4") (pinfunction "4_4") (pintype "passive"))
      (node (ref "J3") (pin "5") (pinfunction "5_5") (pintype "passive"))
      (node (ref "J3") (pin "6") (pinfunction "6_6") (pintype "passive"))
      (node (ref "J3") (pin "7") (pinfunction "7_7") (pintype "passive"))
      (node (ref "J3") (pin "8") (pinfunction "8_8") (pintype "passive"))
      (node (ref "J4") (pin "10") (pinfunction "10_10") (pintype "passive"))
      (node (ref "J4") (pin "11") (pinfunction "11_11") (pintype "passive"))
      (node (ref "J4") (pin "4") (pinfunction "4_4") (pintype "passive"))
      (node (ref "J4") (pin "7") (pinfunction "7_7") (pintype "passive"))
      (node (ref "R10") (pin "1") (pinfunction "1_1") (pintype "passive"))
      (node (ref "R11") (pin "1") (pinfunction "1_1") (pintype "passive"))
      (node (ref "R12") (pin "1") (pinfunction "1_1") (pintype "passive"))
      (node (ref "R13") (pin "1") (pinfunction "1_1") (pintype "passive"))
      (node (ref "R2") (pin "1") (pinfunction "1_1") (pintype "passive"))
      (node (ref "R3") (pin "1") (pinfunction "1_1") (pintype "passive"))
      (node (ref "R4") (pin "1") (pinfunction "1_1") (pintype "passive"))
      (node (ref "R5") (pin "1") (pinfunction "1_1") (pintype "passive"))
      (node (ref "R8") (pin "1") (pinfunction "1_1") (pintype "passive"))
      (node (ref "T3") (pin "11") (pinfunction "11_11") (pintype "passive"))
      (node (ref "U1") (pin "5") (pinfunction "GND_5") (pintype "passive"))
      (node (ref "U2") (pin "29") (pinfunction "PGND_29") (pintype "passive"))
      (node (ref "U2") (pin "3") (pinfunction "GND_3") (pintype "passive"))
      (node (ref "U3") (pin "5") (pinfunction "GND_5") (pintype "passive"))
      (node (ref "USB1") (pin "1") (pinfunction "GND_1") (pintype "passive"))
      (node (ref "USB1") (pin "6") (pinfunction "Hold_6") (pintype "passive"))
      (node (ref "USB1") (pin "7") (pinfunction "Hold_7") (pintype "passive"))
      (node (ref "USB1") (pin "8") (pinfunction "Hold_8") (pintype "passive"))
      (node (ref "USB1") (pin "9") (pinfunction "Hold_9") (pintype "passive"))
      (node (ref "W1") (pin "10") (pinfunction "10_10") (pintype "passive"))
      (node (ref "Z1") (pin "1") (pinfunction "A_1") (pintype "passive"))
      (node (ref "Z2") (pin "1") (pinfunction "A_1") (pintype "passive"))
    )
    (net (code "27") (name "Net-(1-A_POR_BPS)") (class "Default")
      (node (ref "1") (pin "81") (pinfunction "A_POR_BPS_81") (pintype "passive"))
      (node (ref "JP4") (pin "24") (pinfunction "24_24") (pintype "passive"))
    )
    (net (code "28") (name "Net-(1-CTS3_N)") (class "Default")
      (node (ref "1") (pin "9") (pinfunction "CTS3_N_9") (pintype "passive"))
      (node (ref "JP2") (pin "4") (pinfunction "4_4") (pintype "passive"))
    )
    (net (code "29") (name "Net-(1-D2DB_PORST_N)") (class "Default")
      (node (ref "1") (pin "95") (pinfunction "D2DB_PORST_N_95") (pintype "passive"))
      (node (ref "JP4") (pin "10") (pinfunction "10_10") (pintype "passive"))
    )
    (net (code "30") (name "Net-(1-EJTAG-TDO)") (class "Default")
      (node (ref "1") (pin "121") (pinfunction "EJTAG-TDO_121") (pintype "passive"))
      (node (ref "JP3") (pin "19") (pinfunction "19_19") (pintype "passive"))
    )
    (net (code "31") (name "Net-(1-ESW_P0_LED_0)") (class "Default")
      (node (ref "1") (pin "75") (pinfunction "ESW_P0_LED_0_75") (pintype "passive"))
      (node (ref "JP4") (pin "30") (pinfunction "30_30") (pintype "passive"))
    )
    (net (code "32") (name "Net-(1-ESW_P0_LED_1)") (class "Default")
      (node (ref "1") (pin "76") (pinfunction "ESW_P0_LED_1_76") (pintype "passive"))
      (node (ref "JP4") (pin "29") (pinfunction "29_29") (pintype "passive"))
    )
    (net (code "33") (name "Net-(1-ESW_P1_LED_0)") (class "Default")
      (node (ref "1") (pin "74") (pinfunction "ESW_P1_LED_0_74") (pintype "passive"))
      (node (ref "JP4") (pin "31") (pinfunction "31_31") (pintype "passive"))
    )
    (net (code "34") (name "Net-(1-ESW_P2_LED_0)") (class "Default")
      (node (ref "1") (pin "73") (pinfunction "ESW_P2_LED_0_73") (pintype "passive"))
      (node (ref "JP4") (pin "32") (pinfunction "32_32") (pintype "passive"))
    )
    (net (code "35") (name "Net-(1-ESW_P3_LED_0)") (class "Default")
      (node (ref "1") (pin "72") (pinfunction "ESW_P3_LED_0_72") (pintype "passive"))
      (node (ref "JP4") (pin "33") (pinfunction "33_33") (pintype "passive"))
    )
    (net (code "36") (name "Net-(1-ESW_P4_LED_0)") (class "Default")
      (node (ref "1") (pin "71") (pinfunction "ESW_P4_LED_0_71") (pintype "passive"))
      (node (ref "JP4") (pin "34") (pinfunction "34_34") (pintype "passive"))
    )
    (net (code "37") (name "Net-(1-ESW_TXVN_A_P0)") (class "Default")
      (node (ref "1") (pin "29") (pinfunction "ESW_TXVN_A_P0_29") (pintype "passive"))
      (node (ref "T1") (pin "23") (pinfunction "23_23") (pintype "passive"))
    )
    (net (code "38") (name "Net-(1-ESW_TXVN_A_P1)") (class "Default")
      (node (ref "1") (pin "37") (pinfunction "ESW_TXVN_A_P1_37") (pintype "passive"))
      (node (ref "T1") (pin "11") (pinfunction "11_11") (pintype "passive"))
    )
    (net (code "39") (name "Net-(1-ESW_TXVN_A_P2)") (class "Default")
      (node (ref "1") (pin "46") (pinfunction "ESW_TXVN_A_P2_46") (pintype "passive"))
      (node (ref "T2") (pin "23") (pinfunction "23_23") (pintype "passive"))
    )
    (net (code "40") (name "Net-(1-ESW_TXVN_A_P3)") (class "Default")
      (node (ref "1") (pin "55") (pinfunction "ESW_TXVN_A_P3_55") (pintype "passive"))
      (node (ref "T2") (pin "11") (pinfunction "11_11") (pintype "passive"))
    )
    (net (code "41") (name "Net-(1-ESW_TXVN_B_P0)") (class "Default")
      (node (ref "1") (pin "31") (pinfunction "ESW_TXVN_B_P0_31") (pintype "passive"))
      (node (ref "T1") (pin "20") (pinfunction "20_20") (pintype "passive"))
    )
    (net (code "42") (name "Net-(1-ESW_TXVN_B_P1)") (class "Default")
      (node (ref "1") (pin "39") (pinfunction "ESW_TXVN_B_P1_39") (pintype "passive"))
      (node (ref "T1") (pin "8") (pinfunction "8_8") (pintype "passive"))
    )
    (net (code "43") (name "Net-(1-ESW_TXVN_B_P2)") (class "Default")
      (node (ref "1") (pin "48") (pinfunction "ESW_TXVN_B_P2_48") (pintype "passive"))
      (node (ref "T2") (pin "20") (pinfunction "20_20") (pintype "passive"))
    )
    (net (code "44") (name "Net-(1-ESW_TXVN_B_P3)") (class "Default")
      (node (ref "1") (pin "57") (pinfunction "ESW_TXVN_B_P3_57") (pintype "passive"))
      (node (ref "T2") (pin "8") (pinfunction "8_8") (pintype "passive"))
    )
    (net (code "45") (name "Net-(1-ESW_TXVN_B_P4)") (class "Default")
      (node (ref "1") (pin "66") (pinfunction "ESW_TXVN_B_P4_66") (pintype "passive"))
      (node (ref "T3") (pin "8") (pinfunction "8_8") (pintype "passive"))
    )
    (net (code "46") (name "Net-(1-ESW_TXVN_C_P0)") (class "Default")
      (node (ref "1") (pin "33") (pinfunction "ESW_TXVN_C_P0_33") (pintype "passive"))
      (node (ref "T1") (pin "17") (pinfunction "17_17") (pintype "passive"))
    )
    (net (code "47") (name "Net-(1-ESW_TXVN_C_P1)") (class "Default")
      (node (ref "1") (pin "41") (pinfunction "ESW_TXVN_C_P1_41") (pintype "passive"))
      (node (ref "T1") (pin "5") (pinfunction "5_5") (pintype "passive"))
    )
    (net (code "48") (name "Net-(1-ESW_TXVN_C_P2)") (class "Default")
      (node (ref "1") (pin "50") (pinfunction "ESW_TXVN_C_P2_50") (pintype "passive"))
      (node (ref "T2") (pin "17") (pinfunction "17_17") (pintype "passive"))
    )
    (net (code "49") (name "Net-(1-ESW_TXVN_C_P3)") (class "Default")
      (node (ref "1") (pin "59") (pinfunction "ESW_TXVN_C_P3_59") (pintype "passive"))
      (node (ref "T2") (pin "5") (pinfunction "5_5") (pintype "passive"))
    )
    (net (code "50") (name "Net-(1-ESW_TXVN_C_P4)") (class "Default")
      (node (ref "1") (pin "68") (pinfunction "ESW_TXVN_C_P4_68") (pintype "passive"))
      (node (ref "T3") (pin "5") (pinfunction "5_5") (pintype "passive"))
    )
    (net (code "51") (name "Net-(1-ESW_TXVN_D_P0)") (class "Default")
      (node (ref "1") (pin "35") (pinfunction "ESW_TXVN_D_P0_35") (pintype "passive"))
      (node (ref "T1") (pin "14") (pinfunction "14_14") (pintype "passive"))
    )
    (net (code "52") (name "Net-(1-ESW_TXVN_D_P1)") (class "Default")
      (node (ref "1") (pin "43") (pinfunction "ESW_TXVN_D_P1_43") (pintype "passive"))
      (node (ref "T1") (pin "2") (pinfunction "2_2") (pintype "passive"))
    )
    (net (code "53") (name "Net-(1-ESW_TXVN_D_P2)") (class "Default")
      (node (ref "1") (pin "52") (pinfunction "ESW_TXVN_D_P2_52") (pintype "passive"))
      (node (ref "T2") (pin "14") (pinfunction "14_14") (pintype "passive"))
    )
    (net (code "54") (name "Net-(1-ESW_TXVN_D_P3)") (class "Default")
      (node (ref "1") (pin "61") (pinfunction "ESW_TXVN_D_P3_61") (pintype "passive"))
      (node (ref "T2") (pin "2") (pinfunction "2_2") (pintype "passive"))
    )
    (net (code "55") (name "Net-(1-ESW_TXVN_D_P4)") (class "Default")
      (node (ref "1") (pin "70") (pinfunction "ESW_TXVN_D_P4_70") (pintype "passive"))
      (node (ref "T3") (pin "2") (pinfunction "2_2") (pintype "passive"))
    )
    (net (code "56") (name "Net-(1-ESW_TXVP_A_P0)") (class "Default")
      (node (ref "1") (pin "28") (pinfunction "ESW_TXVP_A_P0_28") (pintype "passive"))
      (node (ref "T1") (pin "24") (pinfunction "24_24") (pintype "passive"))
    )
    (net (code "57") (name "Net-(1-ESW_TXVP_A_P1)") (class "Default")
      (node (ref "1") (pin "36") (pinfunction "ESW_TXVP_A_P1_36") (pintype "passive"))
      (node (ref "T1") (pin "12") (pinfunction "12_12") (pintype "passive"))
    )
    (net (code "58") (name "Net-(1-ESW_TXVP_A_P2)") (class "Default")
      (node (ref "1") (pin "45") (pinfunction "ESW_TXVP_A_P2_45") (pintype "passive"))
      (node (ref "T2") (pin "24") (pinfunction "24_24") (pintype "passive"))
    )
    (net (code "59") (name "Net-(1-ESW_TXVP_A_P3)") (class "Default")
      (node (ref "1") (pin "54") (pinfunction "ESW_TXVP_A_P3_54") (pintype "passive"))
      (node (ref "T2") (pin "12") (pinfunction "12_12") (pintype "passive"))
    )
    (net (code "60") (name "Net-(1-ESW_TXVP_A_P4)") (class "Default")
      (node (ref "1") (pin "63") (pinfunction "ESW_TXVP_A_P4_63") (pintype "passive"))
      (node (ref "T3") (pin "12") (pinfunction "12_12") (pintype "passive"))
    )
    (net (code "61") (name "Net-(1-ESW_TXVP_B_P0)") (class "Default")
      (node (ref "1") (pin "30") (pinfunction "ESW_TXVP_B_P0_30") (pintype "passive"))
      (node (ref "T1") (pin "21") (pinfunction "21_21") (pintype "passive"))
    )
    (net (code "62") (name "Net-(1-ESW_TXVP_B_P1)") (class "Default")
      (node (ref "1") (pin "38") (pinfunction "ESW_TXVP_B_P1_38") (pintype "passive"))
      (node (ref "T1") (pin "9") (pinfunction "9_9") (pintype "passive"))
    )
    (net (code "63") (name "Net-(1-ESW_TXVP_B_P2)") (class "Default")
      (node (ref "1") (pin "47") (pinfunction "ESW_TXVP_B_P2_47") (pintype "passive"))
      (node (ref "T2") (pin "21") (pinfunction "21_21") (pintype "passive"))
    )
    (net (code "64") (name "Net-(1-ESW_TXVP_B_P3)") (class "Default")
      (node (ref "1") (pin "56") (pinfunction "ESW_TXVP_B_P3_56") (pintype "passive"))
      (node (ref "T2") (pin "9") (pinfunction "9_9") (pintype "passive"))
    )
    (net (code "65") (name "Net-(1-ESW_TXVP_B_P4)") (class "Default")
      (node (ref "1") (pin "65") (pinfunction "ESW_TXVP_B_P4_65") (pintype "passive"))
      (node (ref "T3") (pin "9") (pinfunction "9_9") (pintype "passive"))
    )
    (net (code "66") (name "Net-(1-ESW_TXVP_C_P0)") (class "Default")
      (node (ref "1") (pin "32") (pinfunction "ESW_TXVP_C_P0_32") (pintype "passive"))
      (node (ref "T1") (pin "18") (pinfunction "18_18") (pintype "passive"))
    )
    (net (code "67") (name "Net-(1-ESW_TXVP_C_P1)") (class "Default")
      (node (ref "1") (pin "40") (pinfunction "ESW_TXVP_C_P1_40") (pintype "passive"))
      (node (ref "T1") (pin "6") (pinfunction "6_6") (pintype "passive"))
    )
    (net (code "68") (name "Net-(1-ESW_TXVP_C_P2)") (class "Default")
      (node (ref "1") (pin "49") (pinfunction "ESW_TXVP_C_P2_49") (pintype "passive"))
      (node (ref "T2") (pin "18") (pinfunction "18_18") (pintype "passive"))
    )
    (net (code "69") (name "Net-(1-ESW_TXVP_C_P3)") (class "Default")
      (node (ref "1") (pin "58") (pinfunction "ESW_TXVP_C_P3_58") (pintype "passive"))
      (node (ref "T2") (pin "6") (pinfunction "6_6") (pintype "passive"))
    )
    (net (code "70") (name "Net-(1-ESW_TXVP_C_P4)") (class "Default")
      (node (ref "1") (pin "67") (pinfunction "ESW_TXVP_C_P4_67") (pintype "passive"))
      (node (ref "T3") (pin "6") (pinfunction "6_6") (pintype "passive"))
    )
    (net (code "71") (name "Net-(1-ESW_TXVP_D_P0)") (class "Default")
      (node (ref "1") (pin "34") (pinfunction "ESW_TXVP_D_P0_34") (pintype "passive"))
      (node (ref "T1") (pin "15") (pinfunction "15_15") (pintype "passive"))
    )
    (net (code "72") (name "Net-(1-ESW_TXVP_D_P1)") (class "Default")
      (node (ref "1") (pin "42") (pinfunction "ESW_TXVP_D_P1_42") (pintype "passive"))
      (node (ref "T1") (pin "3") (pinfunction "3_3") (pintype "passive"))
    )
    (net (code "73") (name "Net-(1-ESW_TXVP_D_P2)") (class "Default")
      (node (ref "1") (pin "51") (pinfunction "ESW_TXVP_D_P2_51") (pintype "passive"))
      (node (ref "T2") (pin "15") (pinfunction "15_15") (pintype "passive"))
    )
    (net (code "74") (name "Net-(1-ESW_TXVP_D_P3)") (class "Default")
      (node (ref "1") (pin "60") (pinfunction "ESW_TXVP_D_P3_60") (pintype "passive"))
      (node (ref "T2") (pin "3") (pinfunction "3_3") (pintype "passive"))
    )
    (net (code "75") (name "Net-(1-ESW_TXVP_D_P4)") (class "Default")
      (node (ref "1") (pin "69") (pinfunction "ESW_TXVP_D_P4_69") (pintype "passive"))
      (node (ref "T3") (pin "3") (pinfunction "3_3") (pintype "passive"))
    )
    (net (code "76") (name "Net-(1-GE_MDC)") (class "Default")
      (node (ref "1") (pin "83") (pinfunction "GE_MDC_83") (pintype "passive"))
      (node (ref "JP4") (pin "22") (pinfunction "22_22") (pintype "passive"))
    )
    (net (code "77") (name "Net-(1-GE_MDIO)") (class "Default")
      (node (ref "1") (pin "82") (pinfunction "GE_MDIO_82") (pintype "passive"))
      (node (ref "JP4") (pin "23") (pinfunction "23_23") (pintype "passive"))
    )
    (net (code "78") (name "Net-(1-GE_RXCLK)") (class "Default")
      (node (ref "1") (pin "91") (pinfunction "GE_RXCLK_91") (pintype "passive"))
      (node (ref "JP4") (pin "14") (pinfunction "14_14") (pintype "passive"))
    )
    (net (code "79") (name "Net-(1-GE_RXD0)") (class "Default")
      (node (ref "1") (pin "89") (pinfunction "GE_RXD0_89") (pintype "passive"))
      (node (ref "JP4") (pin "16") (pinfunction "16_16") (pintype "passive"))
    )
    (net (code "80") (name "Net-(1-GE_RXD1)") (class "Default")
      (node (ref "1") (pin "88") (pinfunction "GE_RXD1_88") (pintype "passive"))
      (node (ref "JP4") (pin "17") (pinfunction "17_17") (pintype "passive"))
    )
    (net (code "81") (name "Net-(1-GE_RXD2)") (class "Default")
      (node (ref "1") (pin "87") (pinfunction "GE_RXD2_87") (pintype "passive"))
      (node (ref "JP4") (pin "18") (pinfunction "18_18") (pintype "passive"))
    )
    (net (code "82") (name "Net-(1-GE_RXD3)") (class "Default")
      (node (ref "1") (pin "86") (pinfunction "GE_RXD3_86") (pintype "passive"))
      (node (ref "JP4") (pin "19") (pinfunction "19_19") (pintype "passive"))
    )
    (net (code "83") (name "Net-(1-GE_RXDV)") (class "Default")
      (node (ref "1") (pin "90") (pinfunction "GE_RXDV_90") (pintype "passive"))
      (node (ref "JP4") (pin "15") (pinfunction "15_15") (pintype "passive"))
    )
    (net (code "84") (name "Net-(1-GE_TXCLK)") (class "Default")
      (node (ref "1") (pin "85") (pinfunction "GE_TXCLK_85") (pintype "passive"))
      (node (ref "JP4") (pin "20") (pinfunction "20_20") (pintype "passive"))
    )
    (net (code "85") (name "Net-(1-GE_TXD0)") (class "Default")
      (node (ref "1") (pin "80") (pinfunction "GE_TXD0_80") (pintype "passive"))
      (node (ref "JP4") (pin "25") (pinfunction "25_25") (pintype "passive"))
    )
    (net (code "86") (name "Net-(1-GE_TXD1)") (class "Default")
      (node (ref "1") (pin "79") (pinfunction "GE_TXD1_79") (pintype "passive"))
      (node (ref "JP4") (pin "26") (pinfunction "26_26") (pintype "passive"))
    )
    (net (code "87") (name "Net-(1-GE_TXD2)") (class "Default")
      (node (ref "1") (pin "78") (pinfunction "GE_TXD2_78") (pintype "passive"))
      (node (ref "JP4") (pin "27") (pinfunction "27_27") (pintype "passive"))
    )
    (net (code "88") (name "Net-(1-GE_TXD3)") (class "Default")
      (node (ref "1") (pin "77") (pinfunction "GE_TXD3_77") (pintype "passive"))
      (node (ref "JP4") (pin "28") (pinfunction "28_28") (pintype "passive"))
    )
    (net (code "89") (name "Net-(1-GE_TXEN)") (class "Default")
      (node (ref "1") (pin "84") (pinfunction "GE_TXEN_84") (pintype "passive"))
      (node (ref "JP4") (pin "21") (pinfunction "21_21") (pintype "passive"))
    )
    (net (code "90") (name "Net-(1-GND-Pad92)") (class "Default")
      (node (ref "1") (pin "92") (pinfunction "GND_92") (pintype "passive"))
      (node (ref "JP4") (pin "13") (pinfunction "13_13") (pintype "passive"))
    )
    (net (code "91") (name "Net-(1-GND-Pad119)") (class "Default")
      (node (ref "1") (pin "119") (pinfunction "GND_119") (pintype "passive"))
      (node (ref "JP3") (pin "21") (pinfunction "21_21") (pintype "passive"))
    )
    (net (code "92") (name "Net-(1-GND-Pad125)") (class "Default")
      (node (ref "1") (pin "125") (pinfunction "GND_125") (pintype "passive"))
      (node (ref "JP3") (pin "15") (pinfunction "15_15") (pintype "passive"))
    )
    (net (code "93") (name "Net-(1-GPIO0)") (class "Default")
      (node (ref "1") (pin "104") (pinfunction "GPIO0_104") (pintype "passive"))
      (node (ref "JP4") (pin "1") (pinfunction "1_1") (pintype "passive"))
    )
    (net (code "94") (name "Net-(1-I2C_SCLK)") (class "Default")
      (node (ref "1") (pin "96") (pinfunction "I2C_SCLK_96") (pintype "passive"))
      (node (ref "JP4") (pin "9") (pinfunction "9_9") (pintype "passive"))
    )
    (net (code "95") (name "Net-(1-I2C_SD)") (class "Default")
      (node (ref "1") (pin "97") (pinfunction "I2C_SD_97") (pintype "passive"))
      (node (ref "JP4") (pin "8") (pinfunction "8_8") (pintype "passive"))
    )
    (net (code "96") (name "Net-(1-JTCLK)") (class "Default")
      (node (ref "1") (pin "124") (pinfunction "JTCLK_124") (pintype "passive"))
      (node (ref "JP3") (pin "18") (pinfunction "18_18") (pintype "passive"))
    )
    (net (code "97") (name "Net-(1-JTDI)") (class "Default")
      (node (ref "1") (pin "122") (pinfunction "JTDI_122") (pintype "passive"))
      (node (ref "JP3") (pin "20") (pinfunction "20_20") (pintype "passive"))
    )
    (net (code "98") (name "Net-(1-JTMS)") (class "Default")
      (node (ref "1") (pin "120") (pinfunction "JTMS_120") (pintype "passive"))
      (node (ref "JP3") (pin "22") (pinfunction "22_22") (pintype "passive"))
    )
    (net (code "99") (name "Net-(1-JTRST_N)") (class "Default")
      (node (ref "1") (pin "123") (pinfunction "JTRST_N_123") (pintype "passive"))
      (node (ref "JP3") (pin "17") (pinfunction "17_17") (pintype "passive"))
    )
    (net (code "100") (name "Net-(1-MT6605_IRQ)") (class "Default")
      (node (ref "1") (pin "15") (pinfunction "MT6605_IRQ_15") (pintype "passive"))
      (node (ref "JP2") (pin "2") (pinfunction "2_2") (pintype "passive"))
    )
    (net (code "101") (name "Net-(1-ND_ALE)") (class "Default")
      (node (ref "1") (pin "138") (pinfunction "ND_ALE_138") (pintype "passive"))
      (node (ref "JP3") (pin "4") (pinfunction "4_4") (pintype "passive"))
    )
    (net (code "102") (name "Net-(1-ND_CLE)") (class "Default")
      (node (ref "1") (pin "137") (pinfunction "ND_CLE_137") (pintype "passive"))
      (node (ref "JP3") (pin "3") (pinfunction "3_3") (pintype "passive"))
    )
    (net (code "103") (name "Net-(1-ND_CS_N)") (class "Default")
      (node (ref "1") (pin "136") (pinfunction "ND_CS_N_136") (pintype "passive"))
      (node (ref "JP3") (pin "6") (pinfunction "6_6") (pintype "passive"))
    )
    (net (code "104") (name "Net-(1-ND_D0)") (class "Default")
      (node (ref "1") (pin "133") (pinfunction "ND_D0_133") (pintype "passive"))
      (node (ref "JP3") (pin "7") (pinfunction "7_7") (pintype "passive"))
    )
    (net (code "105") (name "Net-(1-ND_D1)") (class "Default")
      (node (ref "1") (pin "132") (pinfunction "ND_D1_132") (pintype "passive"))
      (node (ref "JP3") (pin "10") (pinfunction "10_10") (pintype "passive"))
    )
    (net (code "106") (name "Net-(1-ND_D2)") (class "Default")
      (node (ref "1") (pin "131") (pinfunction "ND_D2_131") (pintype "passive"))
      (node (ref "JP3") (pin "9") (pinfunction "9_9") (pintype "passive"))
    )
    (net (code "107") (name "Net-(1-ND_D3)") (class "Default")
      (node (ref "1") (pin "130") (pinfunction "ND_D3_130") (pintype "passive"))
      (node (ref "JP3") (pin "12") (pinfunction "12_12") (pintype "passive"))
    )
    (net (code "108") (name "Net-(1-ND_D4)") (class "Default")
      (node (ref "1") (pin "129") (pinfunction "ND_D4_129") (pintype "passive"))
      (node (ref "JP3") (pin "11") (pinfunction "11_11") (pintype "passive"))
    )
    (net (code "109") (name "Net-(1-ND_D5)") (class "Default")
      (node (ref "1") (pin "128") (pinfunction "ND_D5_128") (pintype "passive"))
      (node (ref "JP3") (pin "14") (pinfunction "14_14") (pintype "passive"))
    )
    (net (code "110") (name "Net-(1-ND_D6)") (class "Default")
      (node (ref "1") (pin "127") (pinfunction "ND_D6_127") (pintype "passive"))
      (node (ref "JP3") (pin "13") (pinfunction "13_13") (pintype "passive"))
    )
    (net (code "111") (name "Net-(1-ND_D7)") (class "Default")
      (node (ref "1") (pin "126") (pinfunction "ND_D7_126") (pintype "passive"))
      (node (ref "JP3") (pin "16") (pinfunction "16_16") (pintype "passive"))
    )
    (net (code "112") (name "Net-(1-ND_RB_N)") (class "Default")
      (node (ref "1") (pin "134") (pinfunction "ND_RB_N_134") (pintype "passive"))
      (node (ref "JP3") (pin "8") (pinfunction "8_8") (pintype "passive"))
    )
    (net (code "113") (name "Net-(1-ND_RE_N)") (class "Default")
      (node (ref "1") (pin "135") (pinfunction "ND_RE_N_135") (pintype "passive"))
      (node (ref "JP3") (pin "5") (pinfunction "5_5") (pintype "passive"))
    )
    (net (code "114") (name "Net-(1-ND_WE_N)") (class "Default")
      (node (ref "1") (pin "139") (pinfunction "ND_WE_N_139") (pintype "passive"))
      (node (ref "JP3") (pin "1") (pinfunction "1_1") (pintype "passive"))
    )
    (net (code "115") (name "Net-(1-ND_WP)") (class "Default")
      (node (ref "1") (pin "140") (pinfunction "ND_WP_140") (pintype "passive"))
      (node (ref "JP3") (pin "2") (pinfunction "2_2") (pintype "passive"))
    )
    (net (code "116") (name "Net-(1-PCIE_CK0_M)") (class "Default")
      (node (ref "1") (pin "118") (pinfunction "PCIE_CK0_M_118") (pintype "passive"))
      (node (ref "JP3") (pin "24") (pinfunction "24_24") (pintype "passive"))
    )
    (net (code "117") (name "Net-(1-PCIE_CK0_P)") (class "Default")
      (node (ref "1") (pin "117") (pinfunction "PCIE_CK0_P_117") (pintype "passive"))
      (node (ref "JP3") (pin "23") (pinfunction "23_23") (pintype "passive"))
    )
    (net (code "118") (name "Net-(1-PCIE_CK1_M)") (class "Default")
      (node (ref "1") (pin "110") (pinfunction "PCIE_CK1_M_110") (pintype "passive"))
      (node (ref "JP3") (pin "30") (pinfunction "30_30") (pintype "passive"))
    )
    (net (code "119") (name "Net-(1-PCIE_CK1_P)") (class "Default")
      (node (ref "1") (pin "111") (pinfunction "PCIE_CK1_P_111") (pintype "passive"))
      (node (ref "JP3") (pin "29") (pinfunction "29_29") (pintype "passive"))
    )
    (net (code "120") (name "Net-(1-PCIE_RXN0)") (class "Default")
      (node (ref "1") (pin "114") (pinfunction "PCIE_RXN0_114") (pintype "passive"))
      (node (ref "JP3") (pin "28") (pinfunction "28_28") (pintype "passive"))
    )
    (net (code "121") (name "Net-(1-PCIE_RXN1)") (class "Default")
      (node (ref "1") (pin "109") (pinfunction "PCIE_RXN1_109") (pintype "passive"))
      (node (ref "JP3") (pin "31") (pinfunction "31_31") (pintype "passive"))
    )
    (net (code "122") (name "Net-(1-PCIE_RXP0)") (class "Default")
      (node (ref "1") (pin "113") (pinfunction "PCIE_RXP0_113") (pintype "passive"))
      (node (ref "JP3") (pin "27") (pinfunction "27_27") (pintype "passive"))
    )
    (net (code "123") (name "Net-(1-PCIE_RXP1)") (class "Default")
      (node (ref "1") (pin "108") (pinfunction "PCIE_RXP1_108") (pintype "passive"))
      (node (ref "JP3") (pin "32") (pinfunction "32_32") (pintype "passive"))
    )
    (net (code "124") (name "Net-(1-PCIE_TX0_M)") (class "Default")
      (node (ref "1") (pin "115") (pinfunction "PCIE_TX0_M_115") (pintype "passive"))
      (node (ref "JP3") (pin "25") (pinfunction "25_25") (pintype "passive"))
    )
    (net (code "125") (name "Net-(1-PCIE_TX0_P)") (class "Default")
      (node (ref "1") (pin "116") (pinfunction "PCIE_TX0_P_116") (pintype "passive"))
      (node (ref "JP3") (pin "26") (pinfunction "26_26") (pintype "passive"))
    )
    (net (code "126") (name "Net-(1-PCIE_TX1_M)") (class "Default")
      (node (ref "1") (pin "107") (pinfunction "PCIE_TX1_M_107") (pintype "passive"))
      (node (ref "JP3") (pin "33") (pinfunction "33_33") (pintype "passive"))
    )
    (net (code "127") (name "Net-(1-PCIE_TX1_P)") (class "Default")
      (node (ref "1") (pin "106") (pinfunction "PCIE_TX1_P_106") (pintype "passive"))
      (node (ref "JP3") (pin "34") (pinfunction "34_34") (pintype "passive"))
    )
    (net (code "128") (name "Net-(1-RTS2_N)") (class "Default")
      (node (ref "1") (pin "14") (pinfunction "RTS2_N_14") (pintype "passive"))
      (node (ref "JP2") (pin "3") (pinfunction "3_3") (pintype "passive"))
    )
    (net (code "129") (name "Net-(1-RTS3_N)") (class "Default")
      (node (ref "1") (pin "16") (pinfunction "RTS3_N_16") (pintype "passive"))
      (node (ref "JP2") (pin "1") (pinfunction "1_1") (pintype "passive"))
    )
    (net (code "130") (name "Net-(1-SSUSB_RXN)") (class "Default")
      (node (ref "1") (pin "23") (pinfunction "SSUSB_RXN_23") (pintype "passive"))
      (node (ref "J4") (pin "5") (pinfunction "5_5") (pintype "passive"))
    )
    (net (code "131") (name "Net-(1-SSUSB_RXP)") (class "Default")
      (node (ref "1") (pin "22") (pinfunction "SSUSB_RXP_22") (pintype "passive"))
      (node (ref "J4") (pin "6") (pinfunction "6_6") (pintype "passive"))
    )
    (net (code "132") (name "Net-(1-SSUSB_TXN)") (class "Default")
      (node (ref "1") (pin "21") (pinfunction "SSUSB_TXN_21") (pintype "passive"))
      (node (ref "J4") (pin "8") (pinfunction "8_8") (pintype "passive"))
    )
    (net (code "133") (name "Net-(1-SSUSB_TXP)") (class "Default")
      (node (ref "1") (pin "20") (pinfunction "SSUSB_TXP_20") (pintype "passive"))
      (node (ref "J4") (pin "9") (pinfunction "9_9") (pintype "passive"))
    )
    (net (code "134") (name "Net-(1-USB_DM)") (class "Default")
      (node (ref "1") (pin "26") (pinfunction "USB_DM_26") (pintype "passive"))
      (node (ref "J4") (pin "2") (pinfunction "2_2") (pintype "passive"))
    )
    (net (code "135") (name "Net-(1-USB_DM_1P)") (class "Default")
      (node (ref "1") (pin "18") (pinfunction "USB_DM_1P_18") (pintype "passive"))
      (node (ref "J3") (pin "2") (pinfunction "2_2") (pintype "passive"))
    )
    (net (code "136") (name "Net-(1-USB_DP)") (class "Default")
      (node (ref "1") (pin "25") (pinfunction "USB_DP_25") (pintype "passive"))
      (node (ref "J4") (pin "3") (pinfunction "3_3") (pintype "passive"))
    )
    (net (code "137") (name "Net-(1-USB_DP_1P)") (class "Default")
      (node (ref "1") (pin "17") (pinfunction "USB_DP_1P_17") (pintype "passive"))
      (node (ref "J3") (pin "3") (pinfunction "3_3") (pintype "passive"))
    )
    (net (code "138") (name "Net-(1-WPS)") (class "Default")
      (node (ref "1") (pin "112") (pinfunction "WPS_112") (pintype "passive"))
      (node (ref "Default1") (pin "1") (pinfunction "1_1") (pintype "passive"))
    )
    (net (code "139") (name "Net-(C2-Pad2)") (class "Default")
      (node (ref "C2") (pin "2") (pinfunction "2_2") (pintype "passive"))
      (node (ref "R4") (pin "2") (pinfunction "2_2") (pintype "passive"))
    )
    (net (code "140") (name "Net-(C14-Pad2)") (class "Default")
      (node (ref "C14") (pin "2") (pinfunction "2_2") (pintype "passive"))
      (node (ref "R12") (pin "2") (pinfunction "2_2") (pintype "passive"))
    )
    (net (code "141") (name "Net-(C23-Pad1)") (class "Default")
      (node (ref "C23") (pin "1") (pinfunction "1_1") (pintype "passive"))
      (node (ref "C47") (pin "1") (pinfunction "1_1") (pintype "passive"))
      (node (ref "R19") (pin "1") (pinfunction "1_1") (pintype "passive"))
      (node (ref "R20") (pin "1") (pinfunction "1_1") (pintype "passive"))
      (node (ref "R21") (pin "1") (pinfunction "1_1") (pintype "passive"))
      (node (ref "R22") (pin "1") (pinfunction "1_1") (pintype "passive"))
      (node (ref "R23") (pin "1") (pinfunction "1_1") (pintype "passive"))
      (node (ref "R24") (pin "1") (pinfunction "1_1") (pintype "passive"))
      (node (ref "R25") (pin "1") (pinfunction "1_1") (pintype "passive"))
      (node (ref "R26") (pin "1") (pinfunction "1_1") (pintype "passive"))
      (node (ref "R27") (pin "1") (pinfunction "1_1") (pintype "passive"))
      (node (ref "R28") (pin "1") (pinfunction "1_1") (pintype "passive"))
      (node (ref "R29") (pin "1") (pinfunction "1_1") (pintype "passive"))
      (node (ref "R30") (pin "1") (pinfunction "1_1") (pintype "passive"))
      (node (ref "R31") (pin "1") (pinfunction "1_1") (pintype "passive"))
      (node (ref "R32") (pin "1") (pinfunction "1_1") (pintype "passive"))
      (node (ref "R33") (pin "1") (pinfunction "1_1") (pintype "passive"))
      (node (ref "R34") (pin "1") (pinfunction "1_1") (pintype "passive"))
      (node (ref "R35") (pin "1") (pinfunction "1_1") (pintype "passive"))
      (node (ref "R36") (pin "1") (pinfunction "1_1") (pintype "passive"))
      (node (ref "R37") (pin "1") (pinfunction "1_1") (pintype "passive"))
      (node (ref "R38") (pin "1") (pinfunction "1_1") (pintype "passive"))
    )
    (net (code "142") (name "Net-(C27-Pad2)") (class "Default")
      (node (ref "C27") (pin "2") (pinfunction "2_2") (pintype "passive"))
      (node (ref "T1") (pin "22") (pinfunction "22_22") (pintype "passive"))
    )
    (net (code "143") (name "Net-(C28-Pad2)") (class "Default")
      (node (ref "C28") (pin "2") (pinfunction "2_2") (pintype "passive"))
      (node (ref "T1") (pin "19") (pinfunction "19_19") (pintype "passive"))
    )
    (net (code "144") (name "Net-(C29-Pad2)") (class "Default")
      (node (ref "C29") (pin "2") (pinfunction "2_2") (pintype "passive"))
      (node (ref "T1") (pin "16") (pinfunction "16_16") (pintype "passive"))
    )
    (net (code "145") (name "Net-(C30-Pad2)") (class "Default")
      (node (ref "C30") (pin "2") (pinfunction "2_2") (pintype "passive"))
      (node (ref "T1") (pin "13") (pinfunction "13_13") (pintype "passive"))
    )
    (net (code "146") (name "Net-(C31-Pad2)") (class "Default")
      (node (ref "C31") (pin "2") (pinfunction "2_2") (pintype "passive"))
      (node (ref "T1") (pin "10") (pinfunction "10_10") (pintype "passive"))
    )
    (net (code "147") (name "Net-(C32-Pad2)") (class "Default")
      (node (ref "C32") (pin "2") (pinfunction "2_2") (pintype "passive"))
      (node (ref "T1") (pin "7") (pinfunction "7_7") (pintype "passive"))
    )
    (net (code "148") (name "Net-(C33-Pad2)") (class "Default")
      (node (ref "C33") (pin "2") (pinfunction "2_2") (pintype "passive"))
      (node (ref "T1") (pin "4") (pinfunction "4_4") (pintype "passive"))
    )
    (net (code "149") (name "Net-(C34-Pad2)") (class "Default")
      (node (ref "C34") (pin "2") (pinfunction "2_2") (pintype "passive"))
      (node (ref "T1") (pin "1") (pinfunction "1_1") (pintype "passive"))
    )
    (net (code "150") (name "Net-(C35-Pad2)") (class "Default")
      (node (ref "C35") (pin "2") (pinfunction "2_2") (pintype "passive"))
      (node (ref "T2") (pin "22") (pinfunction "22_22") (pintype "passive"))
    )
    (net (code "151") (name "Net-(C36-Pad2)") (class "Default")
      (node (ref "C36") (pin "2") (pinfunction "2_2") (pintype "passive"))
      (node (ref "T2") (pin "19") (pinfunction "19_19") (pintype "passive"))
    )
    (net (code "152") (name "Net-(C37-Pad2)") (class "Default")
      (node (ref "C37") (pin "2") (pinfunction "2_2") (pintype "passive"))
      (node (ref "T2") (pin "16") (pinfunction "16_16") (pintype "passive"))
    )
    (net (code "153") (name "Net-(C38-Pad2)") (class "Default")
      (node (ref "C38") (pin "2") (pinfunction "2_2") (pintype "passive"))
      (node (ref "T2") (pin "13") (pinfunction "13_13") (pintype "passive"))
    )
    (net (code "154") (name "Net-(C39-Pad2)") (class "Default")
      (node (ref "C39") (pin "2") (pinfunction "2_2") (pintype "passive"))
      (node (ref "T2") (pin "10") (pinfunction "10_10") (pintype "passive"))
    )
    (net (code "155") (name "Net-(C40-Pad2)") (class "Default")
      (node (ref "C40") (pin "2") (pinfunction "2_2") (pintype "passive"))
      (node (ref "T2") (pin "7") (pinfunction "7_7") (pintype "passive"))
    )
    (net (code "156") (name "Net-(C41-Pad2)") (class "Default")
      (node (ref "C41") (pin "2") (pinfunction "2_2") (pintype "passive"))
      (node (ref "T2") (pin "4") (pinfunction "4_4") (pintype "passive"))
    )
    (net (code "157") (name "Net-(C42-Pad2)") (class "Default")
      (node (ref "C42") (pin "2") (pinfunction "2_2") (pintype "passive"))
      (node (ref "T2") (pin "1") (pinfunction "1_1") (pintype "passive"))
    )
    (net (code "158") (name "Net-(C43-Pad2)") (class "Default")
      (node (ref "C43") (pin "2") (pinfunction "2_2") (pintype "passive"))
      (node (ref "T3") (pin "10") (pinfunction "10_10") (pintype "passive"))
    )
    (net (code "159") (name "Net-(C44-Pad2)") (class "Default")
      (node (ref "C44") (pin "2") (pinfunction "2_2") (pintype "passive"))
      (node (ref "T3") (pin "7") (pinfunction "7_7") (pintype "passive"))
    )
    (net (code "160") (name "Net-(C45-Pad2)") (class "Default")
      (node (ref "C45") (pin "2") (pinfunction "2_2") (pintype "passive"))
      (node (ref "T3") (pin "4") (pinfunction "4_4") (pintype "passive"))
    )
    (net (code "161") (name "Net-(C46-Pad2)") (class "Default")
      (node (ref "C46") (pin "2") (pinfunction "2_2") (pintype "passive"))
      (node (ref "T3") (pin "1") (pinfunction "1_1") (pintype "passive"))
    )
    (net (code "162") (name "Net-(D1-Pad2)") (class "Default")
      (node (ref "D1") (pin "2") (pinfunction "2_2") (pintype "passive"))
      (node (ref "R15") (pin "1") (pinfunction "1_1") (pintype "passive"))
    )
    (net (code "163") (name "Net-(P1-Pad1)") (class "Default")
      (node (ref "P1") (pin "1") (pinfunction "1_1") (pintype "passive"))
      (node (ref "T1") (pin "25") (pinfunction "25_25") (pintype "passive"))
    )
    (net (code "164") (name "Net-(P1-Pad2)") (class "Default")
      (node (ref "P1") (pin "2") (pinfunction "2_2") (pintype "passive"))
      (node (ref "T1") (pin "26") (pinfunction "26_26") (pintype "passive"))
    )
    (net (code "165") (name "Net-(P1-Pad3)") (class "Default")
      (node (ref "P1") (pin "3") (pinfunction "3_3") (pintype "passive"))
      (node (ref "T1") (pin "28") (pinfunction "28_28") (pintype "passive"))
    )
    (net (code "166") (name "Net-(P1-Pad4)") (class "Default")
      (node (ref "P1") (pin "4") (pinfunction "4_4") (pintype "passive"))
      (node (ref "T1") (pin "31") (pinfunction "31_31") (pintype "passive"))
    )
    (net (code "167") (name "Net-(P1-Pad5)") (class "Default")
      (node (ref "P1") (pin "5") (pinfunction "5_5") (pintype "passive"))
      (node (ref "T1") (pin "32") (pinfunction "32_32") (pintype "passive"))
    )
    (net (code "168") (name "Net-(P1-Pad6)") (class "Default")
      (node (ref "P1") (pin "6") (pinfunction "6_6") (pintype "passive"))
      (node (ref "T1") (pin "29") (pinfunction "29_29") (pintype "passive"))
    )
    (net (code "169") (name "Net-(P1-Pad7)") (class "Default")
      (node (ref "P1") (pin "7") (pinfunction "7_7") (pintype "passive"))
      (node (ref "T1") (pin "34") (pinfunction "34_34") (pintype "passive"))
    )
    (net (code "170") (name "Net-(P1-Pad8)") (class "Default")
      (node (ref "P1") (pin "8") (pinfunction "8_8") (pintype "passive"))
      (node (ref "T1") (pin "35") (pinfunction "35_35") (pintype "passive"))
    )
    (net (code "171") (name "Net-(P1-Pad9)") (class "Default")
      (node (ref "P1") (pin "9") (pinfunction "9_9") (pintype "passive"))
      (node (ref "T1") (pin "37") (pinfunction "37_37") (pintype "passive"))
    )
    (net (code "172") (name "Net-(P1-Pad10)") (class "Default")
      (node (ref "P1") (pin "10") (pinfunction "10_10") (pintype "passive"))
      (node (ref "T1") (pin "38") (pinfunction "38_38") (pintype "passive"))
    )
    (net (code "173") (name "Net-(P1-Pad11)") (class "Default")
      (node (ref "P1") (pin "11") (pinfunction "11_11") (pintype "passive"))
      (node (ref "T1") (pin "40") (pinfunction "40_40") (pintype "passive"))
    )
    (net (code "174") (name "Net-(P1-Pad12)") (class "Default")
      (node (ref "P1") (pin "12") (pinfunction "12_12") (pintype "passive"))
      (node (ref "T1") (pin "43") (pinfunction "43_43") (pintype "passive"))
    )
    (net (code "175") (name "Net-(P1-Pad13)") (class "Default")
      (node (ref "P1") (pin "13") (pinfunction "13_13") (pintype "passive"))
      (node (ref "T1") (pin "44") (pinfunction "44_44") (pintype "passive"))
    )
    (net (code "176") (name "Net-(P1-Pad14)") (class "Default")
      (node (ref "P1") (pin "14") (pinfunction "14_14") (pintype "passive"))
      (node (ref "T1") (pin "41") (pinfunction "41_41") (pintype "passive"))
    )
    (net (code "177") (name "Net-(P1-Pad15)") (class "Default")
      (node (ref "P1") (pin "15") (pinfunction "15_15") (pintype "passive"))
      (node (ref "T1") (pin "46") (pinfunction "46_46") (pintype "passive"))
    )
    (net (code "178") (name "Net-(P1-Pad16)") (class "Default")
      (node (ref "P1") (pin "16") (pinfunction "16_16") (pintype "passive"))
      (node (ref "T1") (pin "47") (pinfunction "47_47") (pintype "passive"))
    )
    (net (code "179") (name "Net-(P1-Pad17)") (class "Default")
      (node (ref "P1") (pin "17") (pinfunction "17_17") (pintype "passive"))
      (node (ref "T2") (pin "25") (pinfunction "25_25") (pintype "passive"))
    )
    (net (code "180") (name "Net-(P1-Pad18)") (class "Default")
      (node (ref "P1") (pin "18") (pinfunction "18_18") (pintype "passive"))
      (node (ref "T2") (pin "26") (pinfunction "26_26") (pintype "passive"))
    )
    (net (code "181") (name "Net-(P1-Pad19)") (class "Default")
      (node (ref "P1") (pin "19") (pinfunction "19_19") (pintype "passive"))
      (node (ref "T2") (pin "28") (pinfunction "28_28") (pintype "passive"))
    )
    (net (code "182") (name "Net-(P1-Pad20)") (class "Default")
      (node (ref "P1") (pin "20") (pinfunction "20_20") (pintype "passive"))
      (node (ref "T2") (pin "31") (pinfunction "31_31") (pintype "passive"))
    )
    (net (code "183") (name "Net-(P1-Pad21)") (class "Default")
      (node (ref "P1") (pin "21") (pinfunction "21_21") (pintype "passive"))
      (node (ref "T2") (pin "32") (pinfunction "32_32") (pintype "passive"))
    )
    (net (code "184") (name "Net-(P1-Pad22)") (class "Default")
      (node (ref "P1") (pin "22") (pinfunction "22_22") (pintype "passive"))
      (node (ref "T2") (pin "29") (pinfunction "29_29") (pintype "passive"))
    )
    (net (code "185") (name "Net-(P1-Pad23)") (class "Default")
      (node (ref "P1") (pin "23") (pinfunction "23_23") (pintype "passive"))
      (node (ref "T2") (pin "34") (pinfunction "34_34") (pintype "passive"))
    )
    (net (code "186") (name "Net-(P1-Pad24)") (class "Default")
      (node (ref "P1") (pin "24") (pinfunction "24_24") (pintype "passive"))
      (node (ref "T2") (pin "35") (pinfunction "35_35") (pintype "passive"))
    )
    (net (code "187") (name "Net-(P1-Pad25)") (class "Default")
      (node (ref "P1") (pin "25") (pinfunction "25_25") (pintype "passive"))
      (node (ref "T2") (pin "37") (pinfunction "37_37") (pintype "passive"))
    )
    (net (code "188") (name "Net-(P1-Pad26)") (class "Default")
      (node (ref "P1") (pin "26") (pinfunction "26_26") (pintype "passive"))
      (node (ref "T2") (pin "38") (pinfunction "38_38") (pintype "passive"))
    )
    (net (code "189") (name "Net-(P1-Pad27)") (class "Default")
      (node (ref "P1") (pin "27") (pinfunction "27_27") (pintype "passive"))
      (node (ref "T2") (pin "40") (pinfunction "40_40") (pintype "passive"))
    )
    (net (code "190") (name "Net-(P1-Pad28)") (class "Default")
      (node (ref "P1") (pin "28") (pinfunction "28_28") (pintype "passive"))
      (node (ref "T2") (pin "43") (pinfunction "43_43") (pintype "passive"))
    )
    (net (code "191") (name "Net-(P1-Pad29)") (class "Default")
      (node (ref "P1") (pin "29") (pinfunction "29_29") (pintype "passive"))
      (node (ref "T2") (pin "44") (pinfunction "44_44") (pintype "passive"))
    )
    (net (code "192") (name "Net-(P1-Pad30)") (class "Default")
      (node (ref "P1") (pin "30") (pinfunction "30_30") (pintype "passive"))
      (node (ref "T2") (pin "41") (pinfunction "41_41") (pintype "passive"))
    )
    (net (code "193") (name "Net-(P1-Pad31)") (class "Default")
      (node (ref "P1") (pin "31") (pinfunction "31_31") (pintype "passive"))
      (node (ref "T2") (pin "46") (pinfunction "46_46") (pintype "passive"))
    )
    (net (code "194") (name "Net-(P1-Pad32)") (class "Default")
      (node (ref "P1") (pin "32") (pinfunction "32_32") (pintype "passive"))
      (node (ref "T2") (pin "47") (pinfunction "47_47") (pintype "passive"))
    )
    (net (code "195") (name "Net-(R8-Pad2)") (class "Default")
      (node (ref "R8") (pin "2") (pinfunction "2_2") (pintype "passive"))
      (node (ref "U2") (pin "11") (pinfunction "SUSPEND_11") (pintype "passive"))
    )
    (net (code "196") (name "Net-(R19-Pad2)") (class "Default")
      (node (ref "R19") (pin "2") (pinfunction "2_2") (pintype "passive"))
      (node (ref "T1") (pin "27") (pinfunction "27_27") (pintype "passive"))
    )
    (net (code "197") (name "Net-(R20-Pad2)") (class "Default")
      (node (ref "R20") (pin "2") (pinfunction "2_2") (pintype "passive"))
      (node (ref "T1") (pin "30") (pinfunction "30_30") (pintype "passive"))
    )
    (net (code "198") (name "Net-(R21-Pad2)") (class "Default")
      (node (ref "R21") (pin "2") (pinfunction "2_2") (pintype "passive"))
      (node (ref "T1") (pin "33") (pinfunction "33_33") (pintype "passive"))
    )
    (net (code "199") (name "Net-(R22-Pad2)") (class "Default")
      (node (ref "R22") (pin "2") (pinfunction "2_2") (pintype "passive"))
      (node (ref "T1") (pin "36") (pinfunction "36_36") (pintype "passive"))
    )
    (net (code "200") (name "Net-(R23-Pad2)") (class "Default")
      (node (ref "R23") (pin "2") (pinfunction "2_2") (pintype "passive"))
      (node (ref "T1") (pin "39") (pinfunction "39_39") (pintype "passive"))
    )
    (net (code "201") (name "Net-(R24-Pad2)") (class "Default")
      (node (ref "R24") (pin "2") (pinfunction "2_2") (pintype "passive"))
      (node (ref "T1") (pin "42") (pinfunction "42_42") (pintype "passive"))
    )
    (net (code "202") (name "Net-(R25-Pad2)") (class "Default")
      (node (ref "R25") (pin "2") (pinfunction "2_2") (pintype "passive"))
      (node (ref "T1") (pin "45") (pinfunction "45_45") (pintype "passive"))
    )
    (net (code "203") (name "Net-(R26-Pad2)") (class "Default")
      (node (ref "R26") (pin "2") (pinfunction "2_2") (pintype "passive"))
      (node (ref "T1") (pin "48") (pinfunction "48_48") (pintype "passive"))
    )
    (net (code "204") (name "Net-(R27-Pad2)") (class "Default")
      (node (ref "R27") (pin "2") (pinfunction "2_2") (pintype "passive"))
      (node (ref "T2") (pin "27") (pinfunction "27_27") (pintype "passive"))
    )
    (net (code "205") (name "Net-(R28-Pad2)") (class "Default")
      (node (ref "R28") (pin "2") (pinfunction "2_2") (pintype "passive"))
      (node (ref "T2") (pin "30") (pinfunction "30_30") (pintype "passive"))
    )
    (net (code "206") (name "Net-(R29-Pad2)") (class "Default")
      (node (ref "R29") (pin "2") (pinfunction "2_2") (pintype "passive"))
      (node (ref "T2") (pin "33") (pinfunction "33_33") (pintype "passive"))
    )
    (net (code "207") (name "Net-(R30-Pad2)") (class "Default")
      (node (ref "R30") (pin "2") (pinfunction "2_2") (pintype "passive"))
      (node (ref "T2") (pin "36") (pinfunction "36_36") (pintype "passive"))
    )
    (net (code "208") (name "Net-(R31-Pad2)") (class "Default")
      (node (ref "R31") (pin "2") (pinfunction "2_2") (pintype "passive"))
      (node (ref "T2") (pin "39") (pinfunction "39_39") (pintype "passive"))
    )
    (net (code "209") (name "Net-(R32-Pad2)") (class "Default")
      (node (ref "R32") (pin "2") (pinfunction "2_2") (pintype "passive"))
      (node (ref "T2") (pin "42") (pinfunction "42_42") (pintype "passive"))
    )
    (net (code "210") (name "Net-(R33-Pad2)") (class "Default")
      (node (ref "R33") (pin "2") (pinfunction "2_2") (pintype "passive"))
      (node (ref "T2") (pin "45") (pinfunction "45_45") (pintype "passive"))
    )
    (net (code "211") (name "Net-(R34-Pad2)") (class "Default")
      (node (ref "R34") (pin "2") (pinfunction "2_2") (pintype "passive"))
      (node (ref "T2") (pin "48") (pinfunction "48_48") (pintype "passive"))
    )
    (net (code "212") (name "Net-(R35-Pad2)") (class "Default")
      (node (ref "R35") (pin "2") (pinfunction "2_2") (pintype "passive"))
      (node (ref "T3") (pin "15") (pinfunction "15_15") (pintype "passive"))
    )
    (net (code "213") (name "Net-(R36-Pad2)") (class "Default")
      (node (ref "R36") (pin "2") (pinfunction "2_2") (pintype "passive"))
      (node (ref "T3") (pin "18") (pinfunction "18_18") (pintype "passive"))
    )
    (net (code "214") (name "Net-(R37-Pad2)") (class "Default")
      (node (ref "R37") (pin "2") (pinfunction "2_2") (pintype "passive"))
      (node (ref "T3") (pin "21") (pinfunction "21_21") (pintype "passive"))
    )
    (net (code "215") (name "Net-(R38-Pad2)") (class "Default")
      (node (ref "R38") (pin "2") (pinfunction "2_2") (pintype "passive"))
      (node (ref "T3") (pin "24") (pinfunction "24_24") (pintype "passive"))
    )
    (net (code "216") (name "Net-(T3-Pad13)") (class "Default")
      (node (ref "T3") (pin "13") (pinfunction "13_13") (pintype "passive"))
      (node (ref "W1") (pin "1") (pinfunction "1_1") (pintype "passive"))
    )
    (net (code "217") (name "Net-(T3-Pad14)") (class "Default")
      (node (ref "T3") (pin "14") (pinfunction "14_14") (pintype "passive"))
      (node (ref "W1") (pin "2") (pinfunction "2_2") (pintype "passive"))
    )
    (net (code "218") (name "Net-(T3-Pad16)") (class "Default")
      (node (ref "T3") (pin "16") (pinfunction "16_16") (pintype "passive"))
      (node (ref "W1") (pin "3") (pinfunction "3_3") (pintype "passive"))
    )
    (net (code "219") (name "Net-(T3-Pad17)") (class "Default")
      (node (ref "T3") (pin "17") (pinfunction "17_17") (pintype "passive"))
      (node (ref "W1") (pin "6") (pinfunction "6_6") (pintype "passive"))
    )
    (net (code "220") (name "Net-(T3-Pad19)") (class "Default")
      (node (ref "T3") (pin "19") (pinfunction "19_19") (pintype "passive"))
      (node (ref "W1") (pin "4") (pinfunction "4_4") (pintype "passive"))
    )
    (net (code "221") (name "Net-(T3-Pad20)") (class "Default")
      (node (ref "T3") (pin "20") (pinfunction "20_20") (pintype "passive"))
      (node (ref "W1") (pin "5") (pinfunction "5_5") (pintype "passive"))
    )
    (net (code "222") (name "Net-(T3-Pad22)") (class "Default")
      (node (ref "T3") (pin "22") (pinfunction "22_22") (pintype "passive"))
      (node (ref "W1") (pin "7") (pinfunction "7_7") (pintype "passive"))
    )
    (net (code "223") (name "Net-(T3-Pad23)") (class "Default")
      (node (ref "T3") (pin "23") (pinfunction "23_23") (pintype "passive"))
      (node (ref "W1") (pin "8") (pinfunction "8_8") (pintype "passive"))
    )
    (net (code "224") (name "Net-(U1-BST)") (class "Default")
      (node (ref "C8") (pin "1") (pinfunction "1_1") (pintype "passive"))
      (node (ref "U1") (pin "8") (pinfunction "BST_8") (pintype "passive"))
    )
    (net (code "225") (name "Net-(U1-COMP)") (class "Default")
      (node (ref "C1") (pin "1") (pinfunction "1_1") (pintype "passive"))
      (node (ref "C2") (pin "1") (pinfunction "1_1") (pintype "passive"))
      (node (ref "U1") (pin "3") (pinfunction "COMP_3") (pintype "passive"))
    )
    (net (code "226") (name "Net-(U1-EN)") (class "Default")
      (node (ref "R5") (pin "2") (pinfunction "2_2") (pintype "passive"))
      (node (ref "R6") (pin "1") (pinfunction "1_1") (pintype "passive"))
      (node (ref "U1") (pin "2") (pinfunction "EN_2") (pintype "passive"))
    )
    (net (code "227") (name "Net-(U1-FB)") (class "Default")
      (node (ref "R1") (pin "2") (pinfunction "2_2") (pintype "passive"))
      (node (ref "R2") (pin "2") (pinfunction "2_2") (pintype "passive"))
      (node (ref "U1") (pin "4") (pinfunction "FB_4") (pintype "passive"))
    )
    (net (code "228") (name "Net-(U1-SW)") (class "Default")
      (node (ref "C8") (pin "2") (pinfunction "2_2") (pintype "passive"))
      (node (ref "L1") (pin "2") (pinfunction "2_2") (pintype "passive"))
      (node (ref "U1") (pin "1") (pinfunction "SW_1") (pintype "passive"))
      (node (ref "Z1") (pin "2") (pinfunction "K_2") (pintype "passive"))
    )
    (net (code "229") (name "Net-(U1-频率)") (class "Default")
      (node (ref "R3") (pin "2") (pinfunction "2_2") (pintype "passive"))
      (node (ref "U1") (pin "6") (pinfunction "频率_6") (pintype "passive"))
    )
    (net (code "230") (name "Net-(U2-RST)") (class "Default")
      (node (ref "R7") (pin "2") (pinfunction "2_2") (pintype "passive"))
      (node (ref "U2") (pin "9") (pinfunction "RST_9") (pintype "passive"))
    )
    (net (code "231") (name "Net-(U2-TXD)") (class "Default")
      (node (ref "R39") (pin "2") (pinfunction "2_2") (pintype "passive"))
      (node (ref "U2") (pin "26") (pinfunction "TXD_26") (pintype "passive"))
    )
    (net (code "232") (name "Net-(U2-VDD)") (class "Default")
      (node (ref "C3") (pin "2") (pinfunction "2_2") (pintype "passive"))
      (node (ref "R7") (pin "1") (pinfunction "1_1") (pintype "passive"))
      (node (ref "U2") (pin "6") (pinfunction "VDD_6") (pintype "passive"))
    )
    (net (code "233") (name "Net-(U3-BST)") (class "Default")
      (node (ref "C17") (pin "1") (pinfunction "1_1") (pintype "passive"))
      (node (ref "U3") (pin "8") (pinfunction "BST_8") (pintype "passive"))
    )
    (net (code "234") (name "Net-(U3-COMP)") (class "Default")
      (node (ref "C13") (pin "1") (pinfunction "1_1") (pintype "passive"))
      (node (ref "C14") (pin "1") (pinfunction "1_1") (pintype "passive"))
      (node (ref "U3") (pin "3") (pinfunction "COMP_3") (pintype "passive"))
    )
    (net (code "235") (name "Net-(U3-EN)") (class "Default")
      (node (ref "R13") (pin "2") (pinfunction "2_2") (pintype "passive"))
      (node (ref "R14") (pin "1") (pinfunction "1_1") (pintype "passive"))
      (node (ref "U3") (pin "2") (pinfunction "EN_2") (pintype "passive"))
    )
    (net (code "236") (name "Net-(U3-FB)") (class "Default")
      (node (ref "R10") (pin "2") (pinfunction "2_2") (pintype "passive"))
      (node (ref "R9") (pin "2") (pinfunction "2_2") (pintype "passive"))
      (node (ref "U3") (pin "4") (pinfunction "FB_4") (pintype "passive"))
    )
    (net (code "237") (name "Net-(U3-SW)") (class "Default")
      (node (ref "C17") (pin "2") (pinfunction "2_2") (pintype "passive"))
      (node (ref "L2") (pin "2") (pinfunction "2_2") (pintype "passive"))
      (node (ref "U3") (pin "1") (pinfunction "SW_1") (pintype "passive"))
      (node (ref "Z2") (pin "2") (pinfunction "K_2") (pintype "passive"))
    )
    (net (code "238") (name "Net-(U3-频率)") (class "Default")
      (node (ref "R11") (pin "2") (pinfunction "2_2") (pintype "passive"))
      (node (ref "U3") (pin "6") (pinfunction "频率_6") (pintype "passive"))
    )
    (net (code "239") (name "unconnected-(J1-0-Pad1)") (class "Default")
      (node (ref "J1") (pin "1") (pinfunction "0_1") (pintype "passive"))
    )
    (net (code "240") (name "unconnected-(J1-Pad3)") (class "Default")
      (node (ref "J1") (pin "3") (pinfunction "3_3") (pintype "passive"))
    )
    (net (code "241") (name "unconnected-(J1-Pad5)") (class "Default")
      (node (ref "J1") (pin "5") (pinfunction "5_5") (pintype "passive"))
    )
    (net (code "242") (name "unconnected-(J1-Pad6)") (class "Default")
      (node (ref "J1") (pin "6") (pinfunction "6_6") (pintype "passive"))
    )
    (net (code "243") (name "unconnected-(J1-Pad7)") (class "Default")
      (node (ref "J1") (pin "7") (pinfunction "7_7") (pintype "passive"))
    )
    (net (code "244") (name "unconnected-(J1-Pad8)") (class "Default")
      (node (ref "J1") (pin "8") (pinfunction "8_8") (pintype "passive"))
    )
    (net (code "245") (name "unconnected-(J1-Pad10)") (class "Default")
      (node (ref "J1") (pin "10") (pinfunction "10_10") (pintype "passive"))
    )
    (net (code "246") (name "unconnected-(J1-Pad12)") (class "Default")
      (node (ref "J1") (pin "12") (pinfunction "12_12") (pintype "passive"))
    )
    (net (code "247") (name "unconnected-(J1-Pad14)") (class "Default")
      (node (ref "J1") (pin "14") (pinfunction "14_14") (pintype "passive"))
    )
    (net (code "248") (name "unconnected-(J1-Pad16)") (class "Default")
      (node (ref "J1") (pin "16") (pinfunction "16_16") (pintype "passive"))
    )
    (net (code "249") (name "unconnected-(J1-Pad17)") (class "Default")
      (node (ref "J1") (pin "17") (pinfunction "17_17") (pintype "passive"))
    )
    (net (code "250") (name "unconnected-(J1-Pad19)") (class "Default")
      (node (ref "J1") (pin "19") (pinfunction "19_19") (pintype "passive"))
    )
    (net (code "251") (name "unconnected-(J1-Pad20)") (class "Default")
      (node (ref "J1") (pin "20") (pinfunction "20_20") (pintype "passive"))
    )
    (net (code "252") (name "unconnected-(J1-Pad28)") (class "Default")
      (node (ref "J1") (pin "28") (pinfunction "28_28") (pintype "passive"))
    )
    (net (code "253") (name "unconnected-(J1-Pad30)") (class "Default")
      (node (ref "J1") (pin "30") (pinfunction "30_30") (pintype "passive"))
    )
    (net (code "254") (name "unconnected-(J1-Pad32)") (class "Default")
      (node (ref "J1") (pin "32") (pinfunction "32_32") (pintype "passive"))
    )
    (net (code "255") (name "unconnected-(J1-Pad36)") (class "Default")
      (node (ref "J1") (pin "36") (pinfunction "36_36") (pintype "passive"))
    )
    (net (code "256") (name "unconnected-(J1-Pad38)") (class "Default")
      (node (ref "J1") (pin "38") (pinfunction "38_38") (pintype "passive"))
    )
    (net (code "257") (name "unconnected-(J1-Pad45)") (class "Default")
      (node (ref "J1") (pin "45") (pinfunction "45_45") (pintype "passive"))
    )
    (net (code "258") (name "unconnected-(J1-Pad51)") (class "Default")
      (node (ref "J1") (pin "51") (pinfunction "51_51") (pintype "passive"))
    )
    (net (code "259") (name "unconnected-(J1-Pad53)") (class "Default")
      (node (ref "J1") (pin "53") (pinfunction "53_53") (pintype "passive"))
    )
    (net (code "260") (name "unconnected-(J1-Pad54)") (class "Default")
      (node (ref "J1") (pin "54") (pinfunction "54_54") (pintype "passive"))
    )
    (net (code "261") (name "unconnected-(J1-Pad61)") (class "Default")
      (node (ref "J1") (pin "61") (pinfunction "61_61") (pintype "passive"))
    )
    (net (code "262") (name "unconnected-(J1-Pad62)") (class "Default")
      (node (ref "J1") (pin "62") (pinfunction "62_62") (pintype "passive"))
    )
    (net (code "263") (name "unconnected-(J1-Pad67)") (class "Default")
      (node (ref "J1") (pin "67") (pinfunction "67_67") (pintype "passive"))
    )
    (net (code "264") (name "unconnected-(J1-Pad68)") (class "Default")
      (node (ref "J1") (pin "68") (pinfunction "68_68") (pintype "passive"))
    )
    (net (code "265") (name "unconnected-(P1-Pad33)") (class "Default")
      (node (ref "P1") (pin "33") (pinfunction "33_33") (pintype "passive"))
    )
    (net (code "266") (name "unconnected-(P1-Pad34)") (class "Default")
      (node (ref "P1") (pin "34") (pinfunction "34_34") (pintype "passive"))
    )
    (net (code "267") (name "unconnected-(U2-CTS-Pad23)") (class "Default")
      (node (ref "U2") (pin "23") (pinfunction "CTS_23") (pintype "passive"))
    )
    (net (code "268") (name "unconnected-(U2-DCD-Pad1)") (class "Default")
      (node (ref "U2") (pin "1") (pinfunction "DCD_1") (pintype "passive"))
    )
    (net (code "269") (name "unconnected-(U2-DSR-Pad27)") (class "Default")
      (node (ref "U2") (pin "27") (pinfunction "DSR_27") (pintype "passive"))
    )
    (net (code "270") (name "unconnected-(U2-DTR-Pad28)") (class "Default")
      (node (ref "U2") (pin "28") (pinfunction "DTR_28") (pintype "passive"))
    )
    (net (code "271") (name "unconnected-(U2-NC1-Pad10)") (class "Default")
      (node (ref "U2") (pin "10") (pinfunction "NC1_10") (pintype "passive"))
    )
    (net (code "272") (name "unconnected-(U2-NC2-Pad13)") (class "Default")
      (node (ref "U2") (pin "13") (pinfunction "NC2_13") (pintype "passive"))
    )
    (net (code "273") (name "unconnected-(U2-NC3-Pad14)") (class "Default")
      (node (ref "U2") (pin "14") (pinfunction "NC3_14") (pintype "passive"))
    )
    (net (code "274") (name "unconnected-(U2-NC4-Pad15)") (class "Default")
      (node (ref "U2") (pin "15") (pinfunction "NC4_15") (pintype "passive"))
    )
    (net (code "275") (name "unconnected-(U2-NC5-Pad16)") (class "Default")
      (node (ref "U2") (pin "16") (pinfunction "NC5_16") (pintype "passive"))
    )
    (net (code "276") (name "unconnected-(U2-NC6-Pad17)") (class "Default")
      (node (ref "U2") (pin "17") (pinfunction "NC6_17") (pintype "passive"))
    )
    (net (code "277") (name "unconnected-(U2-NC7-Pad18)") (class "Default")
      (node (ref "U2") (pin "18") (pinfunction "NC7_18") (pintype "passive"))
    )
    (net (code "278") (name "unconnected-(U2-NC8-Pad19)") (class "Default")
      (node (ref "U2") (pin "19") (pinfunction "NC8_19") (pintype "passive"))
    )
    (net (code "279") (name "unconnected-(U2-NC9-Pad20)") (class "Default")
      (node (ref "U2") (pin "20") (pinfunction "NC9_20") (pintype "passive"))
    )
    (net (code "280") (name "unconnected-(U2-NC10-Pad21)") (class "Default")
      (node (ref "U2") (pin "21") (pinfunction "NC10_21") (pintype "passive"))
    )
    (net (code "281") (name "unconnected-(U2-NC11-Pad22)") (class "Default")
      (node (ref "U2") (pin "22") (pinfunction "NC11_22") (pintype "passive"))
    )
    (net (code "282") (name "unconnected-(U2-RI-Pad2)") (class "Default")
      (node (ref "U2") (pin "2") (pinfunction "RI_2") (pintype "passive"))
    )
    (net (code "283") (name "unconnected-(U2-RTS-Pad24)") (class "Default")
      (node (ref "U2") (pin "24") (pinfunction "RTS_24") (pintype "passive"))
    )
    (net (code "284") (name "unconnected-(U2-SUSPEND-Pad12)") (class "Default")
      (node (ref "U2") (pin "12") (pinfunction "SUSPEND_12") (pintype "passive"))
    )
    (net (code "285") (name "unconnected-(USB1-ID-Pad2)") (class "Default")
      (node (ref "USB1") (pin "2") (pinfunction "ID_2") (pintype "passive"))
    )
    (net (code "286") (name "unconnected-(W1-Pad9)") (class "Default")
      (node (ref "W1") (pin "9") (pinfunction "9_9") (pintype "passive"))
    )
  )
)
